# EEG_cap_final.net
KiCad netlist of a schematic drawn in EAGLE
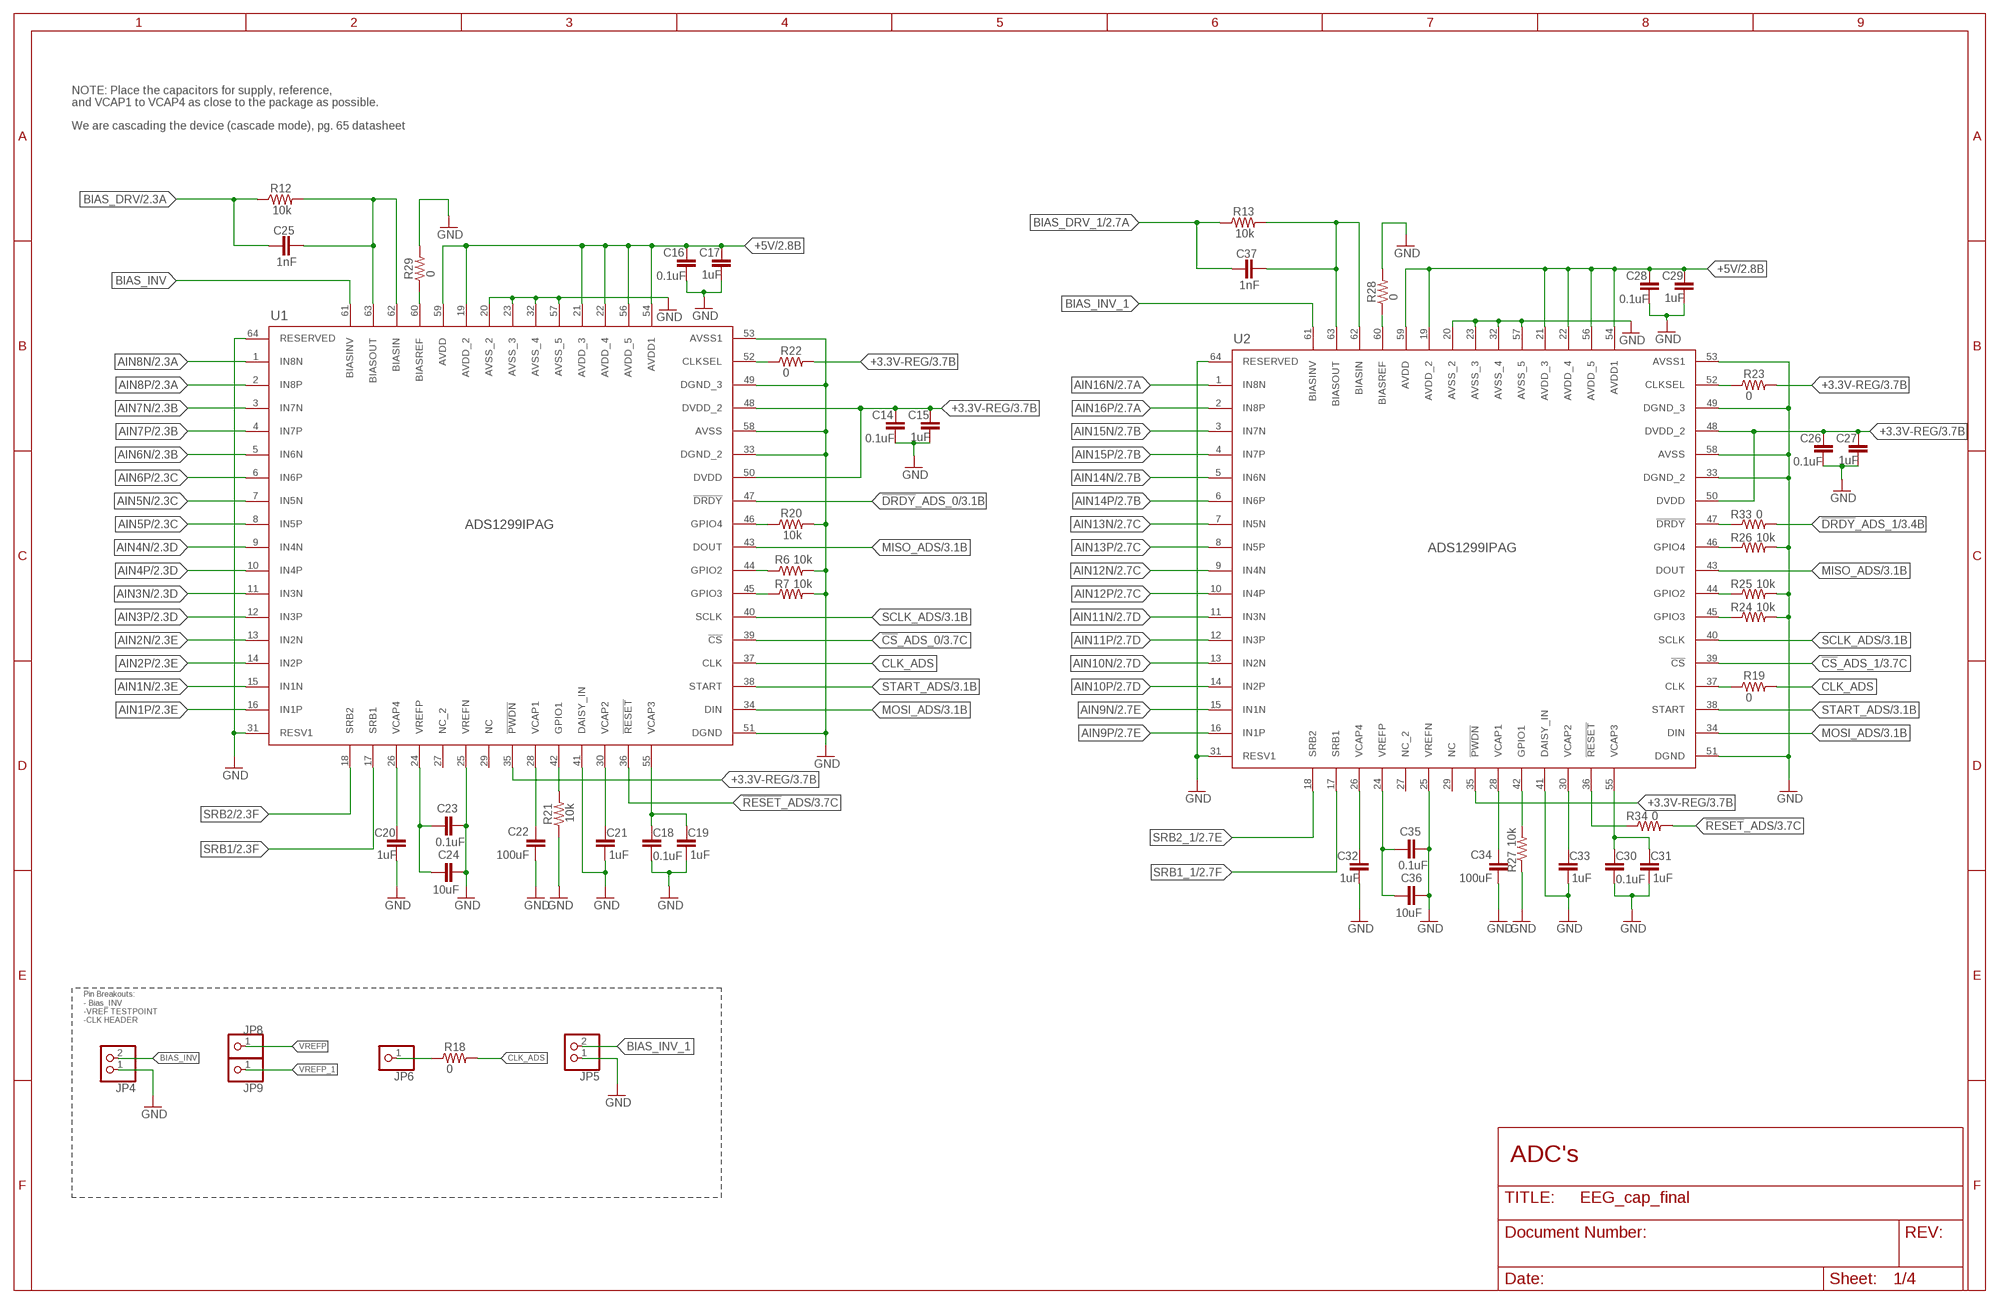
[diagram p0: schematic, sheet 1]
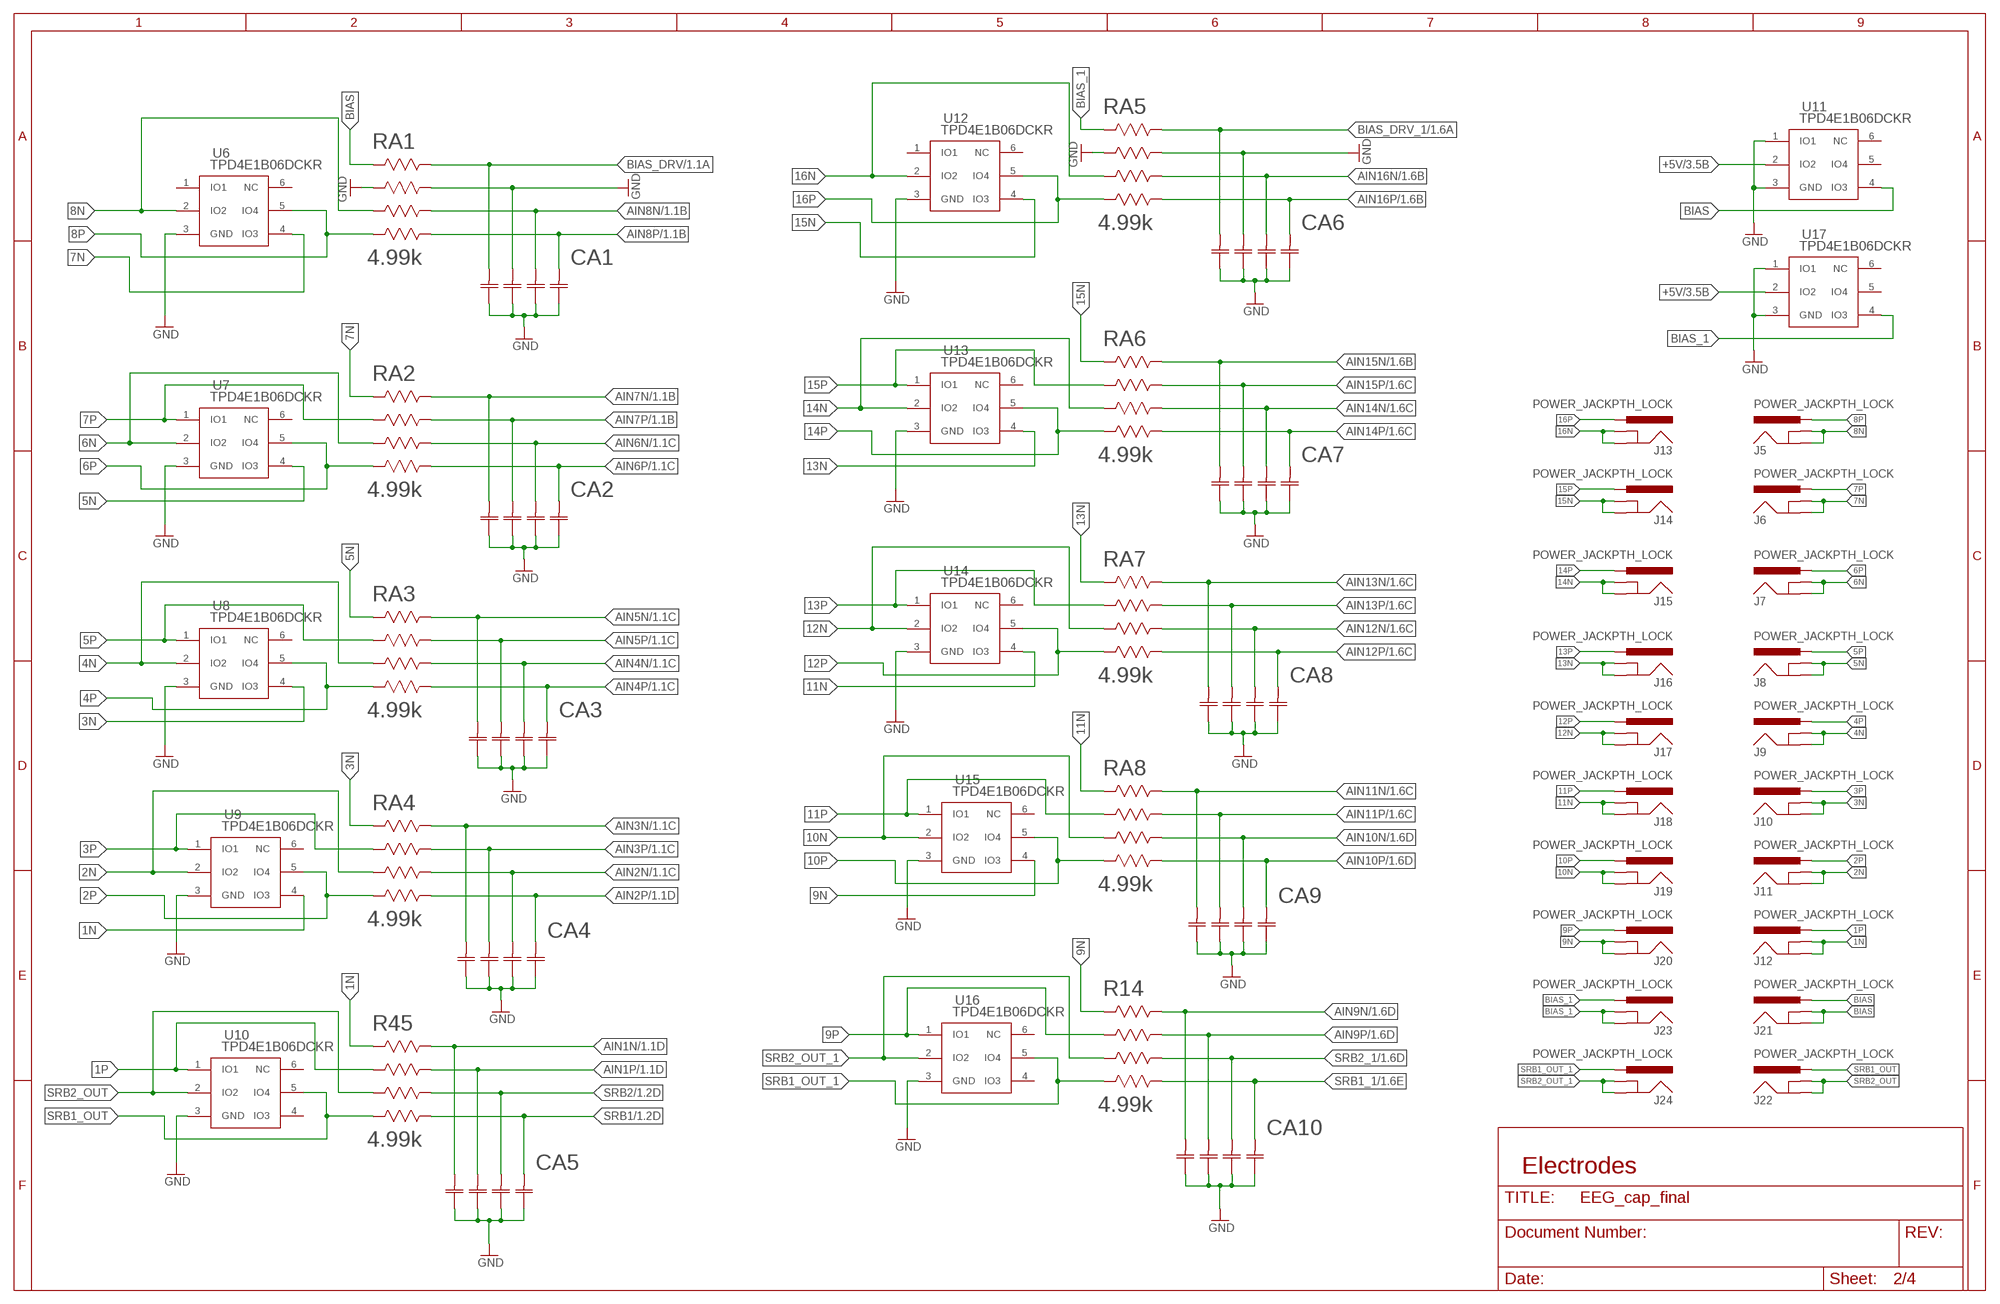
[diagram p1: schematic, sheet 2]
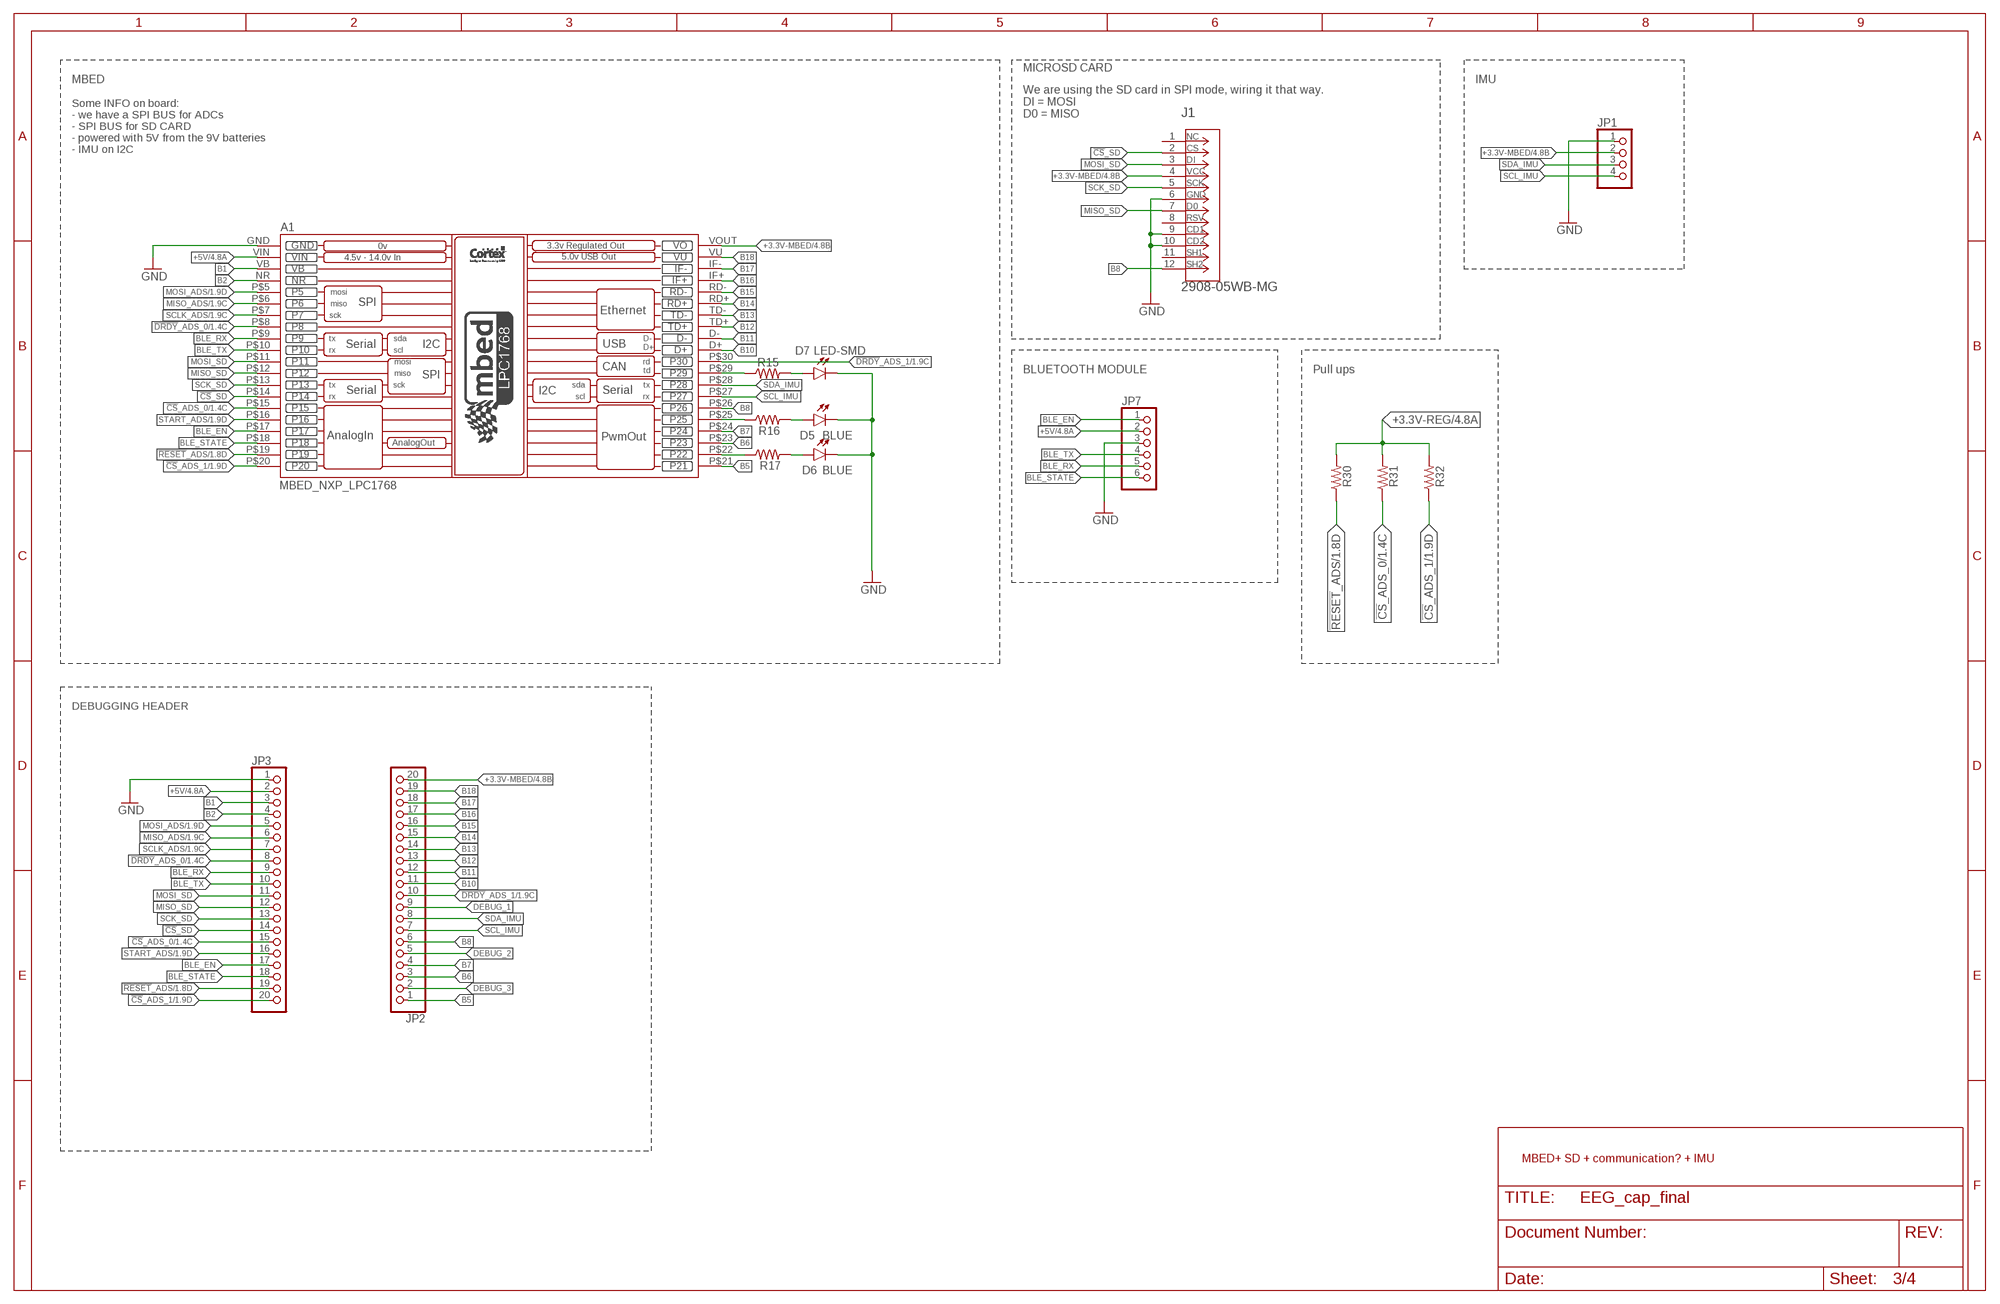
[diagram p2: schematic, sheet 3]
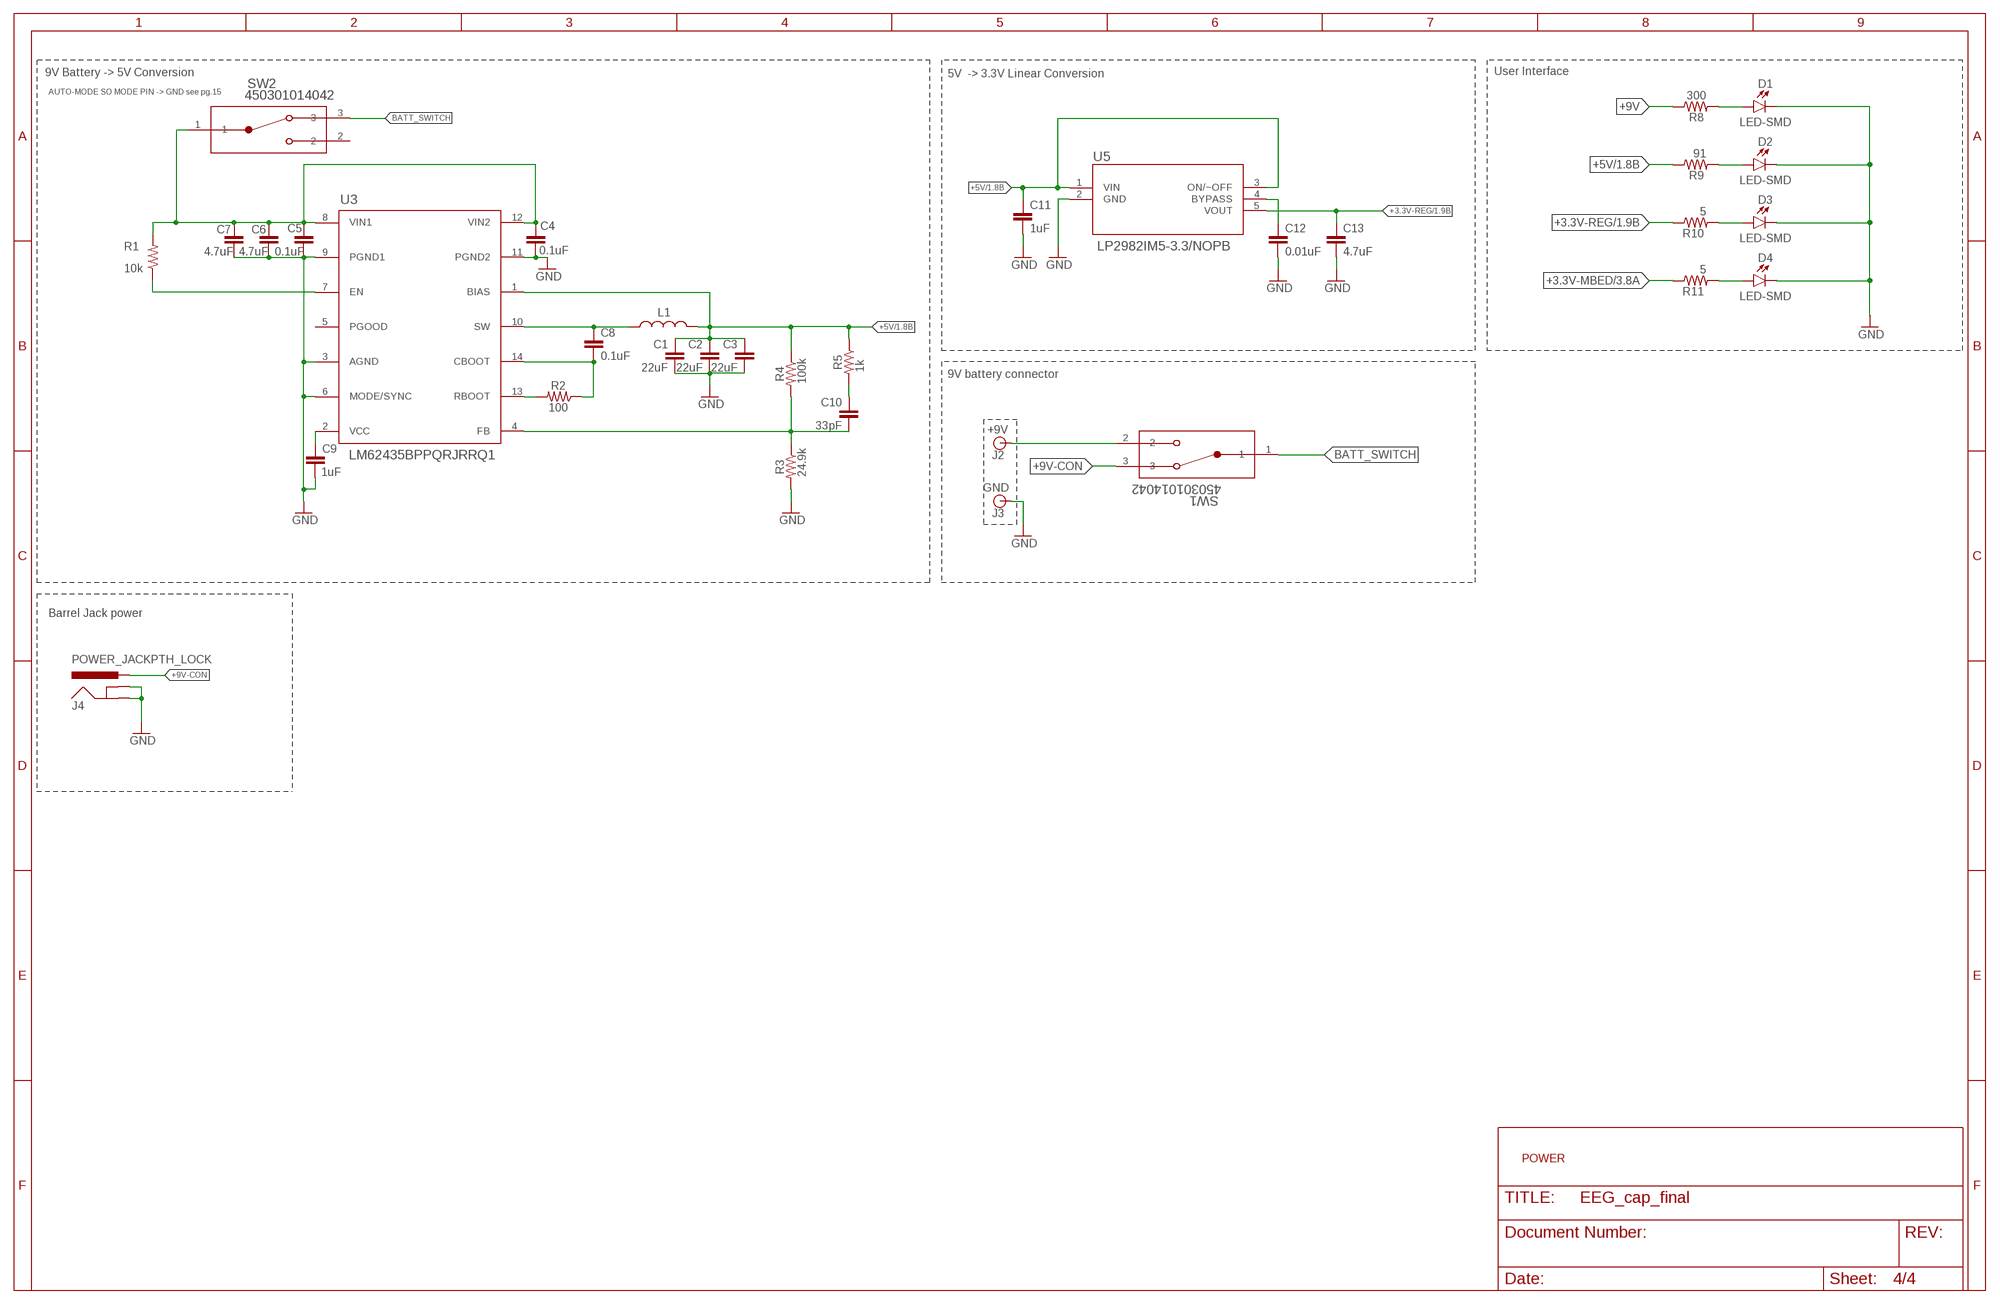
[diagram p3: schematic, sheet 4]

(export (version "E")
  (design (tool "Eeschema 10.0.6"))
  (components
    (comp (ref "C14")
      (value "0.1uF")
      (footprint "eagle-import:C0603")
      (libsource (lib "eagle-import") (part "C-EUC0603"))
    )
    (comp (ref "C15")
      (value "1uF")
      (footprint "eagle-import:C0603")
      (libsource (lib "eagle-import") (part "C-EUC0603"))
    )
    (comp (ref "C16")
      (value "0.1uF")
      (footprint "eagle-import:C0603")
      (libsource (lib "eagle-import") (part "C-EUC0603"))
    )
    (comp (ref "C17")
      (value "1uF")
      (footprint "eagle-import:C0603")
      (libsource (lib "eagle-import") (part "C-EUC0603"))
    )
    (comp (ref "C18")
      (value "0.1uF")
      (footprint "eagle-import:C0603")
      (libsource (lib "eagle-import") (part "C-EUC0603"))
    )
    (comp (ref "C19")
      (value "1uF")
      (footprint "eagle-import:C0603")
      (libsource (lib "eagle-import") (part "C-EUC0603"))
    )
    (comp (ref "C20")
      (value "1uF")
      (footprint "eagle-import:C0603")
      (libsource (lib "eagle-import") (part "C-EUC0603"))
    )
    (comp (ref "C21")
      (value "1uF")
      (footprint "eagle-import:C0603")
      (libsource (lib "eagle-import") (part "C-EUC0603"))
    )
    (comp (ref "C22")
      (value "100uF")
      (footprint "eagle-import:C1210")
      (libsource (lib "eagle-import") (part "C-EUC1210"))
    )
    (comp (ref "C23")
      (value "0.1uF")
      (footprint "eagle-import:C0603")
      (libsource (lib "eagle-import") (part "C-EUC0603"))
    )
    (comp (ref "C24")
      (value "10uF")
      (footprint "eagle-import:C0805")
      (libsource (lib "eagle-import") (part "C-EUC0805"))
    )
    (comp (ref "C25")
      (value "1nF")
      (footprint "eagle-import:C0603")
      (libsource (lib "eagle-import") (part "C-EUC0603"))
    )
    (comp (ref "C26")
      (value "0.1uF")
      (footprint "eagle-import:C0603")
      (libsource (lib "eagle-import") (part "C-EUC0603"))
    )
    (comp (ref "C27")
      (value "1uF")
      (footprint "eagle-import:C0603")
      (libsource (lib "eagle-import") (part "C-EUC0603"))
    )
    (comp (ref "C28")
      (value "0.1uF")
      (footprint "eagle-import:C0603")
      (libsource (lib "eagle-import") (part "C-EUC0603"))
    )
    (comp (ref "C29")
      (value "1uF")
      (footprint "eagle-import:C0603")
      (libsource (lib "eagle-import") (part "C-EUC0603"))
    )
    (comp (ref "C30")
      (value "0.1uF")
      (footprint "eagle-import:C0603")
      (libsource (lib "eagle-import") (part "C-EUC0603"))
    )
    (comp (ref "C31")
      (value "1uF")
      (footprint "eagle-import:C0603")
      (libsource (lib "eagle-import") (part "C-EUC0603"))
    )
    (comp (ref "C32")
      (value "1uF")
      (footprint "eagle-import:C0603")
      (libsource (lib "eagle-import") (part "C-EUC0603"))
    )
    (comp (ref "C33")
      (value "1uF")
      (footprint "eagle-import:C0603")
      (libsource (lib "eagle-import") (part "C-EUC0603"))
    )
    (comp (ref "C34")
      (value "100uF")
      (footprint "eagle-import:C1210")
      (libsource (lib "eagle-import") (part "C-EUC1210"))
    )
    (comp (ref "C35")
      (value "0.1uF")
      (footprint "eagle-import:C0603")
      (libsource (lib "eagle-import") (part "C-EUC0603"))
    )
    (comp (ref "C36")
      (value "10uF")
      (footprint "eagle-import:C0805")
      (libsource (lib "eagle-import") (part "C-EUC0805"))
    )
    (comp (ref "C37")
      (value "1nF")
      (footprint "eagle-import:C0603")
      (libsource (lib "eagle-import") (part "C-EUC0603"))
    )
    (comp (ref "JP4")
      (value "PINHD-1X2")
      (footprint "eagle-import:1X02")
      (libsource (lib "eagle-import") (part "PINHD-1X2"))
    )
    (comp (ref "JP5")
      (value "PINHD-1X2")
      (footprint "eagle-import:1X02")
      (libsource (lib "eagle-import") (part "PINHD-1X2"))
    )
    (comp (ref "JP6")
      (value "PINHD-1X1")
      (footprint "eagle-import:1X01")
      (libsource (lib "eagle-import") (part "PINHD-1X1"))
    )
    (comp (ref "JP8")
      (value "PINHD-1X1")
      (footprint "eagle-import:1X01")
      (libsource (lib "eagle-import") (part "PINHD-1X1"))
    )
    (comp (ref "JP9")
      (value "PINHD-1X1")
      (footprint "eagle-import:1X01")
      (libsource (lib "eagle-import") (part "PINHD-1X1"))
    )
    (comp (ref "R6")
      (value "10k")
      (footprint "eagle-import:R0805")
      (libsource (lib "eagle-import") (part "R-US_R0805"))
    )
    (comp (ref "R7")
      (value "10k")
      (footprint "eagle-import:R0805")
      (libsource (lib "eagle-import") (part "R-US_R0805"))
    )
    (comp (ref "R12")
      (value "10k")
      (footprint "eagle-import:R0805")
      (libsource (lib "eagle-import") (part "R-US_R0805"))
    )
    (comp (ref "R13")
      (value "10k")
      (footprint "eagle-import:R0805")
      (libsource (lib "eagle-import") (part "R-US_R0805"))
    )
    (comp (ref "R18")
      (value "0")
      (footprint "eagle-import:R0805")
      (libsource (lib "eagle-import") (part "R-US_R0805"))
    )
    (comp (ref "R19")
      (value "0")
      (footprint "eagle-import:R0805")
      (libsource (lib "eagle-import") (part "R-US_R0805"))
    )
    (comp (ref "R20")
      (value "10k")
      (footprint "eagle-import:R0805")
      (libsource (lib "eagle-import") (part "R-US_R0805"))
    )
    (comp (ref "R21")
      (value "10k")
      (footprint "eagle-import:R0805")
      (libsource (lib "eagle-import") (part "R-US_R0805"))
    )
    (comp (ref "R22")
      (value "0")
      (footprint "eagle-import:R0805")
      (libsource (lib "eagle-import") (part "R-US_R0805"))
    )
    (comp (ref "R23")
      (value "0")
      (footprint "eagle-import:R0805")
      (libsource (lib "eagle-import") (part "R-US_R0805"))
    )
    (comp (ref "R24")
      (value "10k")
      (footprint "eagle-import:R0805")
      (libsource (lib "eagle-import") (part "R-US_R0805"))
    )
    (comp (ref "R25")
      (value "10k")
      (footprint "eagle-import:R0805")
      (libsource (lib "eagle-import") (part "R-US_R0805"))
    )
    (comp (ref "R26")
      (value "10k")
      (footprint "eagle-import:R0805")
      (libsource (lib "eagle-import") (part "R-US_R0805"))
    )
    (comp (ref "R27")
      (value "10k")
      (footprint "eagle-import:R0805")
      (libsource (lib "eagle-import") (part "R-US_R0805"))
    )
    (comp (ref "R28")
      (value "0")
      (footprint "eagle-import:R0805")
      (libsource (lib "eagle-import") (part "R-US_R0805"))
    )
    (comp (ref "R29")
      (value "0")
      (footprint "eagle-import:R0805")
      (libsource (lib "eagle-import") (part "R-US_R0805"))
    )
    (comp (ref "R33")
      (value "0")
      (footprint "eagle-import:R0805")
      (libsource (lib "eagle-import") (part "R-US_R0805"))
    )
    (comp (ref "R34")
      (value "0")
      (footprint "eagle-import:R0805")
      (libsource (lib "eagle-import") (part "R-US_R0805"))
    )
    (comp (ref "U1")
      (value "ADS1299IPAG")
      (footprint "eagle-import:PAG64_TEX")
      (fields (field (name "COPYRIGHT") "Copyright (C) 2021 Ultra Librarian. All rights reserved."))
      (libsource (lib "eagle-import") (part "ADS1299IPAG"))
    )
    (comp (ref "U2")
      (value "ADS1299IPAG")
      (footprint "eagle-import:PAG64_TEX")
      (fields (field (name "COPYRIGHT") "Copyright (C) 2021 Ultra Librarian. All rights reserved."))
      (libsource (lib "eagle-import") (part "ADS1299IPAG"))
    )
    (comp (ref "CA1")
      (value "4.7nF")
      (footprint "eagle-import:CAP_CA0612_3P2X1P6_YAG")
      (libsource (lib "eagle-import") (part "CAP_ARRAY"))
    )
    (comp (ref "CA2")
      (value "4.7nF")
      (footprint "eagle-import:CAP_CA0612_3P2X1P6_YAG")
      (libsource (lib "eagle-import") (part "CAP_ARRAY"))
    )
    (comp (ref "CA3")
      (value "4.7nF")
      (footprint "eagle-import:CAP_CA0612_3P2X1P6_YAG")
      (libsource (lib "eagle-import") (part "CAP_ARRAY"))
    )
    (comp (ref "CA4")
      (value "4.7nF")
      (footprint "eagle-import:CAP_CA0612_3P2X1P6_YAG")
      (libsource (lib "eagle-import") (part "CAP_ARRAY"))
    )
    (comp (ref "CA5")
      (value "4.7nF")
      (footprint "eagle-import:CAP_CA0612_3P2X1P6_YAG")
      (libsource (lib "eagle-import") (part "CAP_ARRAY"))
    )
    (comp (ref "CA6")
      (value "4.7nF")
      (footprint "eagle-import:CAP_CA0612_3P2X1P6_YAG")
      (libsource (lib "eagle-import") (part "CAP_ARRAY"))
    )
    (comp (ref "CA7")
      (value "4.7nF")
      (footprint "eagle-import:CAP_CA0612_3P2X1P6_YAG")
      (libsource (lib "eagle-import") (part "CAP_ARRAY"))
    )
    (comp (ref "CA8")
      (value "4.7nF")
      (footprint "eagle-import:CAP_CA0612_3P2X1P6_YAG")
      (libsource (lib "eagle-import") (part "CAP_ARRAY"))
    )
    (comp (ref "CA9")
      (value "4.7nF")
      (footprint "eagle-import:CAP_CA0612_3P2X1P6_YAG")
      (libsource (lib "eagle-import") (part "CAP_ARRAY"))
    )
    (comp (ref "CA10")
      (value "4.7nF")
      (footprint "eagle-import:CAP_CA0612_3P2X1P6_YAG")
      (libsource (lib "eagle-import") (part "CAP_ARRAY"))
    )
    (comp (ref "J5")
      (value "POWER_JACKPTH_LOCK")
      (footprint "eagle-import:POWER_JACK_PTH_LOCK")
      (libsource (lib "eagle-import") (part "POWER_JACKPTH_LOCK"))
    )
    (comp (ref "J6")
      (value "POWER_JACKPTH_LOCK")
      (footprint "eagle-import:POWER_JACK_PTH_LOCK")
      (libsource (lib "eagle-import") (part "POWER_JACKPTH_LOCK"))
    )
    (comp (ref "J7")
      (value "POWER_JACKPTH_LOCK")
      (footprint "eagle-import:POWER_JACK_PTH_LOCK")
      (libsource (lib "eagle-import") (part "POWER_JACKPTH_LOCK"))
    )
    (comp (ref "J8")
      (value "POWER_JACKPTH_LOCK")
      (footprint "eagle-import:POWER_JACK_PTH_LOCK")
      (libsource (lib "eagle-import") (part "POWER_JACKPTH_LOCK"))
    )
    (comp (ref "J9")
      (value "POWER_JACKPTH_LOCK")
      (footprint "eagle-import:POWER_JACK_PTH_LOCK")
      (libsource (lib "eagle-import") (part "POWER_JACKPTH_LOCK"))
    )
    (comp (ref "J10")
      (value "POWER_JACKPTH_LOCK")
      (footprint "eagle-import:POWER_JACK_PTH_LOCK")
      (libsource (lib "eagle-import") (part "POWER_JACKPTH_LOCK"))
    )
    (comp (ref "J11")
      (value "POWER_JACKPTH_LOCK")
      (footprint "eagle-import:POWER_JACK_PTH_LOCK")
      (libsource (lib "eagle-import") (part "POWER_JACKPTH_LOCK"))
    )
    (comp (ref "J12")
      (value "POWER_JACKPTH_LOCK")
      (footprint "eagle-import:POWER_JACK_PTH_LOCK")
      (libsource (lib "eagle-import") (part "POWER_JACKPTH_LOCK"))
    )
    (comp (ref "J13")
      (value "POWER_JACKPTH_LOCK")
      (footprint "eagle-import:POWER_JACK_PTH_LOCK")
      (libsource (lib "eagle-import") (part "POWER_JACKPTH_LOCK"))
    )
    (comp (ref "J14")
      (value "POWER_JACKPTH_LOCK")
      (footprint "eagle-import:POWER_JACK_PTH_LOCK")
      (libsource (lib "eagle-import") (part "POWER_JACKPTH_LOCK"))
    )
    (comp (ref "J15")
      (value "POWER_JACKPTH_LOCK")
      (footprint "eagle-import:POWER_JACK_PTH_LOCK")
      (libsource (lib "eagle-import") (part "POWER_JACKPTH_LOCK"))
    )
    (comp (ref "J16")
      (value "POWER_JACKPTH_LOCK")
      (footprint "eagle-import:POWER_JACK_PTH_LOCK")
      (libsource (lib "eagle-import") (part "POWER_JACKPTH_LOCK"))
    )
    (comp (ref "J17")
      (value "POWER_JACKPTH_LOCK")
      (footprint "eagle-import:POWER_JACK_PTH_LOCK")
      (libsource (lib "eagle-import") (part "POWER_JACKPTH_LOCK"))
    )
    (comp (ref "J18")
      (value "POWER_JACKPTH_LOCK")
      (footprint "eagle-import:POWER_JACK_PTH_LOCK")
      (libsource (lib "eagle-import") (part "POWER_JACKPTH_LOCK"))
    )
    (comp (ref "J19")
      (value "POWER_JACKPTH_LOCK")
      (footprint "eagle-import:POWER_JACK_PTH_LOCK")
      (libsource (lib "eagle-import") (part "POWER_JACKPTH_LOCK"))
    )
    (comp (ref "J20")
      (value "POWER_JACKPTH_LOCK")
      (footprint "eagle-import:POWER_JACK_PTH_LOCK")
      (libsource (lib "eagle-import") (part "POWER_JACKPTH_LOCK"))
    )
    (comp (ref "J21")
      (value "POWER_JACKPTH_LOCK")
      (footprint "eagle-import:POWER_JACK_PTH_LOCK")
      (libsource (lib "eagle-import") (part "POWER_JACKPTH_LOCK"))
    )
    (comp (ref "J22")
      (value "POWER_JACKPTH_LOCK")
      (footprint "eagle-import:POWER_JACK_PTH_LOCK")
      (libsource (lib "eagle-import") (part "POWER_JACKPTH_LOCK"))
    )
    (comp (ref "J23")
      (value "POWER_JACKPTH_LOCK")
      (footprint "eagle-import:POWER_JACK_PTH_LOCK")
      (libsource (lib "eagle-import") (part "POWER_JACKPTH_LOCK"))
    )
    (comp (ref "J24")
      (value "POWER_JACKPTH_LOCK")
      (footprint "eagle-import:POWER_JACK_PTH_LOCK")
      (libsource (lib "eagle-import") (part "POWER_JACKPTH_LOCK"))
    )
    (comp (ref "R14")
      (value "4.99k")
      (footprint "eagle-import:BO_CAT16")
      (fields
        (field (name "MANUFACTURER_PART_NUMBER") "CAT16-220J4LF")
        (field (name "COPYRIGHT") "Copyright (C) 2021 Ultra Librarian. All rights reserved.")
      )
      (libsource (lib "eagle-import") (part "CAT16-220J4LF"))
    )
    (comp (ref "R45")
      (value "4.99k")
      (footprint "eagle-import:BO_CAT16")
      (fields
        (field (name "MANUFACTURER_PART_NUMBER") "CAT16-220J4LF")
        (field (name "COPYRIGHT") "Copyright (C) 2021 Ultra Librarian. All rights reserved.")
      )
      (libsource (lib "eagle-import") (part "CAT16-220J4LF"))
    )
    (comp (ref "RA1")
      (value "4.99k")
      (footprint "eagle-import:BO_CAT16")
      (fields
        (field (name "MANUFACTURER_PART_NUMBER") "CAT16-220J4LF")
        (field (name "COPYRIGHT") "Copyright (C) 2021 Ultra Librarian. All rights reserved.")
      )
      (libsource (lib "eagle-import") (part "CAT16-220J4LF"))
    )
    (comp (ref "RA2")
      (value "4.99k")
      (footprint "eagle-import:BO_CAT16")
      (fields
        (field (name "MANUFACTURER_PART_NUMBER") "CAT16-220J4LF")
        (field (name "COPYRIGHT") "Copyright (C) 2021 Ultra Librarian. All rights reserved.")
      )
      (libsource (lib "eagle-import") (part "CAT16-220J4LF"))
    )
    (comp (ref "RA3")
      (value "4.99k")
      (footprint "eagle-import:BO_CAT16")
      (fields
        (field (name "MANUFACTURER_PART_NUMBER") "CAT16-220J4LF")
        (field (name "COPYRIGHT") "Copyright (C) 2021 Ultra Librarian. All rights reserved.")
      )
      (libsource (lib "eagle-import") (part "CAT16-220J4LF"))
    )
    (comp (ref "RA4")
      (value "4.99k")
      (footprint "eagle-import:BO_CAT16")
      (fields
        (field (name "MANUFACTURER_PART_NUMBER") "CAT16-220J4LF")
        (field (name "COPYRIGHT") "Copyright (C) 2021 Ultra Librarian. All rights reserved.")
      )
      (libsource (lib "eagle-import") (part "CAT16-220J4LF"))
    )
    (comp (ref "RA5")
      (value "4.99k")
      (footprint "eagle-import:BO_CAT16")
      (fields
        (field (name "MANUFACTURER_PART_NUMBER") "CAT16-220J4LF")
        (field (name "COPYRIGHT") "Copyright (C) 2021 Ultra Librarian. All rights reserved.")
      )
      (libsource (lib "eagle-import") (part "CAT16-220J4LF"))
    )
    (comp (ref "RA6")
      (value "4.99k")
      (footprint "eagle-import:BO_CAT16")
      (fields
        (field (name "MANUFACTURER_PART_NUMBER") "CAT16-220J4LF")
        (field (name "COPYRIGHT") "Copyright (C) 2021 Ultra Librarian. All rights reserved.")
      )
      (libsource (lib "eagle-import") (part "CAT16-220J4LF"))
    )
    (comp (ref "RA7")
      (value "4.99k")
      (footprint "eagle-import:BO_CAT16")
      (fields
        (field (name "MANUFACTURER_PART_NUMBER") "CAT16-220J4LF")
        (field (name "COPYRIGHT") "Copyright (C) 2021 Ultra Librarian. All rights reserved.")
      )
      (libsource (lib "eagle-import") (part "CAT16-220J4LF"))
    )
    (comp (ref "RA8")
      (value "4.99k")
      (footprint "eagle-import:BO_CAT16")
      (fields
        (field (name "MANUFACTURER_PART_NUMBER") "CAT16-220J4LF")
        (field (name "COPYRIGHT") "Copyright (C) 2021 Ultra Librarian. All rights reserved.")
      )
      (libsource (lib "eagle-import") (part "CAT16-220J4LF"))
    )
    (comp (ref "U6")
      (value "TPD4E1B06DCKR")
      (footprint "eagle-import:DCK6_TEX")
      (fields (field (name "COPYRIGHT") "Copyright (C) 2021 Ultra Librarian. All rights reserved."))
      (libsource (lib "eagle-import") (part "TPD4E1B06DCKR"))
    )
    (comp (ref "U7")
      (value "TPD4E1B06DCKR")
      (footprint "eagle-import:DCK6_TEX")
      (fields (field (name "COPYRIGHT") "Copyright (C) 2021 Ultra Librarian. All rights reserved."))
      (libsource (lib "eagle-import") (part "TPD4E1B06DCKR"))
    )
    (comp (ref "U8")
      (value "TPD4E1B06DCKR")
      (footprint "eagle-import:DCK6_TEX")
      (fields (field (name "COPYRIGHT") "Copyright (C) 2021 Ultra Librarian. All rights reserved."))
      (libsource (lib "eagle-import") (part "TPD4E1B06DCKR"))
    )
    (comp (ref "U9")
      (value "TPD4E1B06DCKR")
      (footprint "eagle-import:DCK6_TEX")
      (fields (field (name "COPYRIGHT") "Copyright (C) 2021 Ultra Librarian. All rights reserved."))
      (libsource (lib "eagle-import") (part "TPD4E1B06DCKR"))
    )
    (comp (ref "U10")
      (value "TPD4E1B06DCKR")
      (footprint "eagle-import:DCK6_TEX")
      (fields (field (name "COPYRIGHT") "Copyright (C) 2021 Ultra Librarian. All rights reserved."))
      (libsource (lib "eagle-import") (part "TPD4E1B06DCKR"))
    )
    (comp (ref "U11")
      (value "TPD4E1B06DCKR")
      (footprint "eagle-import:DCK6_TEX")
      (fields (field (name "COPYRIGHT") "Copyright (C) 2021 Ultra Librarian. All rights reserved."))
      (libsource (lib "eagle-import") (part "TPD4E1B06DCKR"))
    )
    (comp (ref "U12")
      (value "TPD4E1B06DCKR")
      (footprint "eagle-import:DCK6_TEX")
      (fields (field (name "COPYRIGHT") "Copyright (C) 2021 Ultra Librarian. All rights reserved."))
      (libsource (lib "eagle-import") (part "TPD4E1B06DCKR"))
    )
    (comp (ref "U13")
      (value "TPD4E1B06DCKR")
      (footprint "eagle-import:DCK6_TEX")
      (fields (field (name "COPYRIGHT") "Copyright (C) 2021 Ultra Librarian. All rights reserved."))
      (libsource (lib "eagle-import") (part "TPD4E1B06DCKR"))
    )
    (comp (ref "U14")
      (value "TPD4E1B06DCKR")
      (footprint "eagle-import:DCK6_TEX")
      (fields (field (name "COPYRIGHT") "Copyright (C) 2021 Ultra Librarian. All rights reserved."))
      (libsource (lib "eagle-import") (part "TPD4E1B06DCKR"))
    )
    (comp (ref "U15")
      (value "TPD4E1B06DCKR")
      (footprint "eagle-import:DCK6_TEX")
      (fields (field (name "COPYRIGHT") "Copyright (C) 2021 Ultra Librarian. All rights reserved."))
      (libsource (lib "eagle-import") (part "TPD4E1B06DCKR"))
    )
    (comp (ref "U16")
      (value "TPD4E1B06DCKR")
      (footprint "eagle-import:DCK6_TEX")
      (fields (field (name "COPYRIGHT") "Copyright (C) 2021 Ultra Librarian. All rights reserved."))
      (libsource (lib "eagle-import") (part "TPD4E1B06DCKR"))
    )
    (comp (ref "U17")
      (value "TPD4E1B06DCKR")
      (footprint "eagle-import:DCK6_TEX")
      (fields (field (name "COPYRIGHT") "Copyright (C) 2021 Ultra Librarian. All rights reserved."))
      (libsource (lib "eagle-import") (part "TPD4E1B06DCKR"))
    )
    (comp (ref "A1")
      (value "MBED_NXP_LPC1768")
      (footprint "eagle-import:MBED_LPC1768")
      (libsource (lib "eagle-import") (part "MBED_NXP_LPC1768"))
    )
    (comp (ref "D5")
      (value "BLUE")
      (footprint "eagle-import:LED0603")
      (libsource (lib "eagle-import") (part "LED-SMD"))
    )
    (comp (ref "D6")
      (value "BLUE")
      (footprint "eagle-import:LED0603")
      (libsource (lib "eagle-import") (part "LED-SMD"))
    )
    (comp (ref "D7")
      (value "LED-SMD")
      (footprint "eagle-import:LED0603")
      (libsource (lib "eagle-import") (part "LED-SMD"))
    )
    (comp (ref "J1")
      (value "2908-05WB-MG")
      (footprint "eagle-import:CONN_3M_2900")
      (fields (field (name "COPYRIGHT") "Copyright (C) 2021 Ultra Librarian. All rights reserved."))
      (libsource (lib "eagle-import") (part "2908-05WB-MG"))
    )
    (comp (ref "JP1")
      (value "PINHD-1X4")
      (footprint "eagle-import:1X04")
      (libsource (lib "eagle-import") (part "PINHD-1X4"))
    )
    (comp (ref "JP2")
      (value "PINHD-1X20")
      (footprint "eagle-import:1X20")
      (libsource (lib "eagle-import") (part "PINHD-1X20"))
    )
    (comp (ref "JP3")
      (value "PINHD-1X20")
      (footprint "eagle-import:1X20")
      (libsource (lib "eagle-import") (part "PINHD-1X20"))
    )
    (comp (ref "JP7")
      (value "PINHD-1X6")
      (footprint "eagle-import:1X06")
      (libsource (lib "eagle-import") (part "PINHD-1X6"))
    )
    (comp (ref "R15")
      (value "1k")
      (footprint "eagle-import:R0805")
      (libsource (lib "eagle-import") (part "R-US_R0805"))
    )
    (comp (ref "R16")
      (value "1k")
      (footprint "eagle-import:R0805")
      (libsource (lib "eagle-import") (part "R-US_R0805"))
    )
    (comp (ref "R17")
      (value "1k")
      (footprint "eagle-import:R0805")
      (libsource (lib "eagle-import") (part "R-US_R0805"))
    )
    (comp (ref "R30")
      (value "10k")
      (footprint "eagle-import:R0805")
      (libsource (lib "eagle-import") (part "R-US_R0805"))
    )
    (comp (ref "R31")
      (value "1k")
      (footprint "eagle-import:R0805")
      (libsource (lib "eagle-import") (part "R-US_R0805"))
    )
    (comp (ref "R32")
      (value "1k")
      (footprint "eagle-import:R0805")
      (libsource (lib "eagle-import") (part "R-US_R0805"))
    )
    (comp (ref "C1")
      (value "22uF")
      (footprint "eagle-import:C0805")
      (libsource (lib "eagle-import") (part "C-EUC0805"))
    )
    (comp (ref "C2")
      (value "22uF")
      (footprint "eagle-import:C0805")
      (libsource (lib "eagle-import") (part "C-EUC0805"))
    )
    (comp (ref "C3")
      (value "22uF")
      (footprint "eagle-import:C0805")
      (libsource (lib "eagle-import") (part "C-EUC0805"))
    )
    (comp (ref "C4")
      (value "0.1uF")
      (footprint "eagle-import:C0805")
      (libsource (lib "eagle-import") (part "C-EUC0805"))
    )
    (comp (ref "C5")
      (value "0.1uF")
      (footprint "eagle-import:C0805")
      (libsource (lib "eagle-import") (part "C-EUC0805"))
    )
    (comp (ref "C6")
      (value "4.7uF")
      (footprint "eagle-import:C0805")
      (libsource (lib "eagle-import") (part "C-EUC0805"))
    )
    (comp (ref "C7")
      (value "4.7uF")
      (footprint "eagle-import:C0805")
      (libsource (lib "eagle-import") (part "C-EUC0805"))
    )
    (comp (ref "C8")
      (value "0.1uF")
      (footprint "eagle-import:C0805")
      (libsource (lib "eagle-import") (part "C-EUC0805"))
    )
    (comp (ref "C9")
      (value "1uF")
      (footprint "eagle-import:C0805")
      (libsource (lib "eagle-import") (part "C-EUC0805"))
    )
    (comp (ref "C10")
      (value "33pF")
      (footprint "eagle-import:C0805")
      (libsource (lib "eagle-import") (part "C-EUC0805"))
    )
    (comp (ref "C11")
      (value "1uF")
      (footprint "eagle-import:C0805")
      (libsource (lib "eagle-import") (part "C-EUC0805"))
    )
    (comp (ref "C12")
      (value "0.01uF")
      (footprint "eagle-import:C0805")
      (libsource (lib "eagle-import") (part "C-EUC0805"))
    )
    (comp (ref "C13")
      (value "4.7uF")
      (footprint "eagle-import:C0805")
      (libsource (lib "eagle-import") (part "C-EUC0805"))
    )
    (comp (ref "D1")
      (value "LED-SMD")
      (footprint "eagle-import:LED0603")
      (libsource (lib "eagle-import") (part "LED-SMD"))
    )
    (comp (ref "D2")
      (value "LED-SMD")
      (footprint "eagle-import:LED0603")
      (libsource (lib "eagle-import") (part "LED-SMD"))
    )
    (comp (ref "D3")
      (value "LED-SMD")
      (footprint "eagle-import:LED0603")
      (libsource (lib "eagle-import") (part "LED-SMD"))
    )
    (comp (ref "D4")
      (value "LED-SMD")
      (footprint "eagle-import:LED0603")
      (libsource (lib "eagle-import") (part "LED-SMD"))
    )
    (comp (ref "J2")
      (value "+9V")
      (footprint "eagle-import:BANANA_CONN")
      (libsource (lib "eagle-import") (part "BANANA_CONN"))
    )
    (comp (ref "J3")
      (value "GND")
      (footprint "eagle-import:BANANA_CONN")
      (libsource (lib "eagle-import") (part "BANANA_CONN"))
    )
    (comp (ref "J4")
      (value "POWER_JACKPTH_LOCK")
      (footprint "eagle-import:POWER_JACK_PTH_LOCK")
      (libsource (lib "eagle-import") (part "POWER_JACKPTH_LOCK"))
    )
    (comp (ref "L1")
      (value "DFE252010P-1R5M=P2")
      (footprint "eagle-import:INDC2520X100N")
      (fields (field (name "DIGI-KEY_PART_NUMBER") "490-10636-1-ND") (field (name "MF") "Murata"))
      (libsource (lib "eagle-import") (part "DFE252010P-1R5M=P2"))
    )
    (comp (ref "R1")
      (value "10k")
      (footprint "eagle-import:R0805")
      (libsource (lib "eagle-import") (part "R-US_R0805"))
    )
    (comp (ref "R2")
      (value "100")
      (footprint "eagle-import:R0805")
      (libsource (lib "eagle-import") (part "R-US_R0805"))
    )
    (comp (ref "R3")
      (value "24.9k")
      (footprint "eagle-import:R0805")
      (libsource (lib "eagle-import") (part "R-US_R0805"))
    )
    (comp (ref "R4")
      (value "100k")
      (footprint "eagle-import:R0805")
      (libsource (lib "eagle-import") (part "R-US_R0805"))
    )
    (comp (ref "R5")
      (value "1k")
      (footprint "eagle-import:R0805")
      (libsource (lib "eagle-import") (part "R-US_R0805"))
    )
    (comp (ref "R8")
      (value "300")
      (footprint "eagle-import:R0805")
      (libsource (lib "eagle-import") (part "R-US_R0805"))
    )
    (comp (ref "R9")
      (value "91")
      (footprint "eagle-import:R0805")
      (libsource (lib "eagle-import") (part "R-US_R0805"))
    )
    (comp (ref "R10")
      (value "5")
      (footprint "eagle-import:R0805")
      (libsource (lib "eagle-import") (part "R-US_R0805"))
    )
    (comp (ref "R11")
      (value "5")
      (footprint "eagle-import:R0805")
      (libsource (lib "eagle-import") (part "R-US_R0805"))
    )
    (comp (ref "SW1")
      (value "450301014042")
      (footprint "eagle-import:SW_450301014042_WRE")
      (fields (field (name "COPYRIGHT") "Copyright (C) 2021 Ultra Librarian. All rights reserved."))
      (libsource (lib "eagle-import") (part "450301014042"))
    )
    (comp (ref "SW2")
      (value "450301014042")
      (footprint "eagle-import:SW_450301014042_WRE")
      (fields (field (name "COPYRIGHT") "Copyright (C) 2021 Ultra Librarian. All rights reserved."))
      (libsource (lib "eagle-import") (part "450301014042"))
    )
    (comp (ref "U3")
      (value "LM62435BPPQRJRRQ1")
      (footprint "eagle-import:VQFN-HR14_RJR_TEX")
      (fields (field (name "COPYRIGHT") "Copyright (C) 2021 Ultra Librarian. All rights reserved."))
      (libsource (lib "eagle-import") (part "LM62435BPPQRJRRQ1"))
    )
    (comp (ref "U5")
      (value "LP2982IM5-3.3/NOPB")
      (footprint "eagle-import:MF05A")
      (fields (field (name "COPYRIGHT") "Copyright (C) 2021 Ultra Librarian. All rights reserved."))
      (libsource (lib "eagle-import") (part "LP2982IM5-3.3/NOPB"))
    )
  )
  (nets
    (net (code "1") (name "+3.3V-MBED") (class "Default")
      (node (ref "A1") (pin "VOUT") (pinfunction "VO_VOUT") (pintype "passive"))
      (node (ref "J1") (pin "4") (pinfunction "4_4") (pintype "passive"))
      (node (ref "JP1") (pin "2") (pinfunction "2_2") (pintype "passive"))
      (node (ref "JP2") (pin "20") (pinfunction "20_20") (pintype "passive"))
      (node (ref "R11") (pin "1") (pinfunction "1_1") (pintype "passive"))
    )
    (net (code "2") (name "+3.3V-REG") (class "Default")
      (node (ref "C13") (pin "1") (pinfunction "1_1") (pintype "passive"))
      (node (ref "C14") (pin "1") (pinfunction "1_1") (pintype "passive"))
      (node (ref "C15") (pin "1") (pinfunction "1_1") (pintype "passive"))
      (node (ref "C26") (pin "1") (pinfunction "1_1") (pintype "passive"))
      (node (ref "C27") (pin "1") (pinfunction "1_1") (pintype "passive"))
      (node (ref "R10") (pin "1") (pinfunction "1_1") (pintype "passive"))
      (node (ref "R22") (pin "2") (pinfunction "2_2") (pintype "passive"))
      (node (ref "R23") (pin "2") (pinfunction "2_2") (pintype "passive"))
      (node (ref "R30") (pin "2") (pinfunction "2_2") (pintype "passive"))
      (node (ref "R31") (pin "2") (pinfunction "2_2") (pintype "passive"))
      (node (ref "R32") (pin "2") (pinfunction "2_2") (pintype "passive"))
      (node (ref "U1") (pin "35") (pinfunction "~{PWDN}_35") (pintype "power_in"))
      (node (ref "U1") (pin "48") (pinfunction "DVDD_2_48") (pintype "power_in"))
      (node (ref "U1") (pin "50") (pinfunction "DVDD_50") (pintype "power_in"))
      (node (ref "U2") (pin "35") (pinfunction "~{PWDN}_35") (pintype "power_in"))
      (node (ref "U2") (pin "48") (pinfunction "DVDD_2_48") (pintype "power_in"))
      (node (ref "U2") (pin "50") (pinfunction "DVDD_50") (pintype "power_in"))
      (node (ref "U5") (pin "5") (pinfunction "VOUT_5") (pintype "output"))
    )
    (net (code "3") (name "+5V") (class "Default")
      (node (ref "A1") (pin "VIN") (pinfunction "VIN_VIN") (pintype "passive"))
      (node (ref "C1") (pin "1") (pinfunction "1_1") (pintype "passive"))
      (node (ref "C11") (pin "1") (pinfunction "1_1") (pintype "passive"))
      (node (ref "C16") (pin "1") (pinfunction "1_1") (pintype "passive"))
      (node (ref "C17") (pin "1") (pinfunction "1_1") (pintype "passive"))
      (node (ref "C2") (pin "1") (pinfunction "1_1") (pintype "passive"))
      (node (ref "C28") (pin "1") (pinfunction "1_1") (pintype "passive"))
      (node (ref "C29") (pin "1") (pinfunction "1_1") (pintype "passive"))
      (node (ref "C3") (pin "1") (pinfunction "1_1") (pintype "passive"))
      (node (ref "JP3") (pin "2") (pinfunction "2_2") (pintype "passive"))
      (node (ref "JP7") (pin "2") (pinfunction "2_2") (pintype "passive"))
      (node (ref "L1") (pin "2") (pinfunction "2_2") (pintype "passive"))
      (node (ref "R4") (pin "1") (pinfunction "1_1") (pintype "passive"))
      (node (ref "R5") (pin "1") (pinfunction "1_1") (pintype "passive"))
      (node (ref "R9") (pin "1") (pinfunction "1_1") (pintype "passive"))
      (node (ref "U1") (pin "19") (pinfunction "AVDD_2_19") (pintype "power_in"))
      (node (ref "U1") (pin "21") (pinfunction "AVDD_3_21") (pintype "power_in"))
      (node (ref "U1") (pin "22") (pinfunction "AVDD_4_22") (pintype "power_in"))
      (node (ref "U1") (pin "54") (pinfunction "AVDD1_54") (pintype "power_in"))
      (node (ref "U1") (pin "56") (pinfunction "AVDD_5_56") (pintype "power_in"))
      (node (ref "U1") (pin "59") (pinfunction "AVDD_59") (pintype "power_in"))
      (node (ref "U11") (pin "2") (pinfunction "IO2_2") (pintype "bidirectional"))
      (node (ref "U17") (pin "2") (pinfunction "IO2_2") (pintype "bidirectional"))
      (node (ref "U2") (pin "19") (pinfunction "AVDD_2_19") (pintype "power_in"))
      (node (ref "U2") (pin "21") (pinfunction "AVDD_3_21") (pintype "power_in"))
      (node (ref "U2") (pin "22") (pinfunction "AVDD_4_22") (pintype "power_in"))
      (node (ref "U2") (pin "54") (pinfunction "AVDD1_54") (pintype "power_in"))
      (node (ref "U2") (pin "56") (pinfunction "AVDD_5_56") (pintype "power_in"))
      (node (ref "U2") (pin "59") (pinfunction "AVDD_59") (pintype "power_in"))
      (node (ref "U3") (pin "1") (pinfunction "BIAS_1") (pintype "passive"))
      (node (ref "U5") (pin "1") (pinfunction "VIN_1") (pintype "input"))
      (node (ref "U5") (pin "3") (pinfunction "ON/~{OFF}_3") (pintype "passive"))
    )
    (net (code "4") (name "+9V") (class "Default")
      (node (ref "C4") (pin "1") (pinfunction "1_1") (pintype "passive"))
      (node (ref "C5") (pin "1") (pinfunction "1_1") (pintype "passive"))
      (node (ref "C6") (pin "1") (pinfunction "1_1") (pintype "passive"))
      (node (ref "C7") (pin "1") (pinfunction "1_1") (pintype "passive"))
      (node (ref "R1") (pin "2") (pinfunction "2_2") (pintype "passive"))
      (node (ref "R8") (pin "1") (pinfunction "1_1") (pintype "passive"))
      (node (ref "SW2") (pin "1") (pinfunction "1_1") (pintype "passive"))
      (node (ref "U3") (pin "12") (pinfunction "VIN2_12") (pintype "input"))
      (node (ref "U3") (pin "8") (pinfunction "VIN1_8") (pintype "input"))
    )
    (net (code "5") (name "+9V-CON") (class "Default")
      (node (ref "J4") (pin "PWR") (pinfunction "PWR_PWR") (pintype "bidirectional"))
      (node (ref "SW1") (pin "3") (pinfunction "3_3") (pintype "passive"))
    )
    (net (code "6") (name "1N") (class "Default")
      (node (ref "J12") (pin "GND") (pinfunction "GND_GND") (pintype "bidirectional"))
      (node (ref "J12") (pin "GNDBREAK") (pinfunction "GNDBREAK_GNDBREAK") (pintype "bidirectional"))
      (node (ref "R45") (pin "1") (pinfunction "1_1") (pintype "passive"))
      (node (ref "U9") (pin "4") (pinfunction "IO3_4") (pintype "bidirectional"))
    )
    (net (code "7") (name "1P") (class "Default")
      (node (ref "J12") (pin "PWR") (pinfunction "PWR_PWR") (pintype "bidirectional"))
      (node (ref "R45") (pin "2") (pinfunction "2_2") (pintype "passive"))
      (node (ref "U10") (pin "1") (pinfunction "IO1_1") (pintype "bidirectional"))
    )
    (net (code "8") (name "2N") (class "Default")
      (node (ref "J11") (pin "GND") (pinfunction "GND_GND") (pintype "bidirectional"))
      (node (ref "J11") (pin "GNDBREAK") (pinfunction "GNDBREAK_GNDBREAK") (pintype "bidirectional"))
      (node (ref "RA4") (pin "3") (pinfunction "3_3") (pintype "passive"))
      (node (ref "U9") (pin "2") (pinfunction "IO2_2") (pintype "bidirectional"))
    )
    (net (code "9") (name "2P") (class "Default")
      (node (ref "J11") (pin "PWR") (pinfunction "PWR_PWR") (pintype "bidirectional"))
      (node (ref "RA4") (pin "4") (pinfunction "4_4") (pintype "passive"))
      (node (ref "U9") (pin "5") (pinfunction "IO4_5") (pintype "bidirectional"))
    )
    (net (code "10") (name "3N") (class "Default")
      (node (ref "J10") (pin "GND") (pinfunction "GND_GND") (pintype "bidirectional"))
      (node (ref "J10") (pin "GNDBREAK") (pinfunction "GNDBREAK_GNDBREAK") (pintype "bidirectional"))
      (node (ref "RA4") (pin "1") (pinfunction "1_1") (pintype "passive"))
      (node (ref "U8") (pin "4") (pinfunction "IO3_4") (pintype "bidirectional"))
    )
    (net (code "11") (name "3P") (class "Default")
      (node (ref "J10") (pin "PWR") (pinfunction "PWR_PWR") (pintype "bidirectional"))
      (node (ref "RA4") (pin "2") (pinfunction "2_2") (pintype "passive"))
      (node (ref "U9") (pin "1") (pinfunction "IO1_1") (pintype "bidirectional"))
    )
    (net (code "12") (name "4N") (class "Default")
      (node (ref "J9") (pin "GND") (pinfunction "GND_GND") (pintype "bidirectional"))
      (node (ref "J9") (pin "GNDBREAK") (pinfunction "GNDBREAK_GNDBREAK") (pintype "bidirectional"))
      (node (ref "RA3") (pin "3") (pinfunction "3_3") (pintype "passive"))
      (node (ref "U8") (pin "2") (pinfunction "IO2_2") (pintype "bidirectional"))
    )
    (net (code "13") (name "4P") (class "Default")
      (node (ref "J9") (pin "PWR") (pinfunction "PWR_PWR") (pintype "bidirectional"))
      (node (ref "RA3") (pin "4") (pinfunction "4_4") (pintype "passive"))
      (node (ref "U8") (pin "5") (pinfunction "IO4_5") (pintype "bidirectional"))
    )
    (net (code "14") (name "5N") (class "Default")
      (node (ref "J8") (pin "GND") (pinfunction "GND_GND") (pintype "bidirectional"))
      (node (ref "J8") (pin "GNDBREAK") (pinfunction "GNDBREAK_GNDBREAK") (pintype "bidirectional"))
      (node (ref "RA3") (pin "1") (pinfunction "1_1") (pintype "passive"))
      (node (ref "U7") (pin "4") (pinfunction "IO3_4") (pintype "bidirectional"))
    )
    (net (code "15") (name "5P") (class "Default")
      (node (ref "J8") (pin "PWR") (pinfunction "PWR_PWR") (pintype "bidirectional"))
      (node (ref "RA3") (pin "2") (pinfunction "2_2") (pintype "passive"))
      (node (ref "U8") (pin "1") (pinfunction "IO1_1") (pintype "bidirectional"))
    )
    (net (code "16") (name "6N") (class "Default")
      (node (ref "J7") (pin "GND") (pinfunction "GND_GND") (pintype "bidirectional"))
      (node (ref "J7") (pin "GNDBREAK") (pinfunction "GNDBREAK_GNDBREAK") (pintype "bidirectional"))
      (node (ref "RA2") (pin "3") (pinfunction "3_3") (pintype "passive"))
      (node (ref "U7") (pin "2") (pinfunction "IO2_2") (pintype "bidirectional"))
    )
    (net (code "17") (name "6P") (class "Default")
      (node (ref "J7") (pin "PWR") (pinfunction "PWR_PWR") (pintype "bidirectional"))
      (node (ref "RA2") (pin "4") (pinfunction "4_4") (pintype "passive"))
      (node (ref "U7") (pin "5") (pinfunction "IO4_5") (pintype "bidirectional"))
    )
    (net (code "18") (name "7N") (class "Default")
      (node (ref "J6") (pin "GND") (pinfunction "GND_GND") (pintype "bidirectional"))
      (node (ref "J6") (pin "GNDBREAK") (pinfunction "GNDBREAK_GNDBREAK") (pintype "bidirectional"))
      (node (ref "RA2") (pin "1") (pinfunction "1_1") (pintype "passive"))
      (node (ref "U6") (pin "4") (pinfunction "IO3_4") (pintype "bidirectional"))
    )
    (net (code "19") (name "7P") (class "Default")
      (node (ref "J6") (pin "PWR") (pinfunction "PWR_PWR") (pintype "bidirectional"))
      (node (ref "RA2") (pin "2") (pinfunction "2_2") (pintype "passive"))
      (node (ref "U7") (pin "1") (pinfunction "IO1_1") (pintype "bidirectional"))
    )
    (net (code "20") (name "8N") (class "Default")
      (node (ref "J5") (pin "GND") (pinfunction "GND_GND") (pintype "bidirectional"))
      (node (ref "J5") (pin "GNDBREAK") (pinfunction "GNDBREAK_GNDBREAK") (pintype "bidirectional"))
      (node (ref "RA1") (pin "3") (pinfunction "3_3") (pintype "passive"))
      (node (ref "U6") (pin "2") (pinfunction "IO2_2") (pintype "bidirectional"))
    )
    (net (code "21") (name "8P") (class "Default")
      (node (ref "J5") (pin "PWR") (pinfunction "PWR_PWR") (pintype "bidirectional"))
      (node (ref "RA1") (pin "4") (pinfunction "4_4") (pintype "passive"))
      (node (ref "U6") (pin "5") (pinfunction "IO4_5") (pintype "bidirectional"))
    )
    (net (code "22") (name "9N") (class "Default")
      (node (ref "J20") (pin "GND") (pinfunction "GND_GND") (pintype "bidirectional"))
      (node (ref "J20") (pin "GNDBREAK") (pinfunction "GNDBREAK_GNDBREAK") (pintype "bidirectional"))
      (node (ref "R14") (pin "1") (pinfunction "1_1") (pintype "passive"))
      (node (ref "U15") (pin "4") (pinfunction "IO3_4") (pintype "bidirectional"))
    )
    (net (code "23") (name "9P") (class "Default")
      (node (ref "J20") (pin "PWR") (pinfunction "PWR_PWR") (pintype "bidirectional"))
      (node (ref "R14") (pin "2") (pinfunction "2_2") (pintype "passive"))
      (node (ref "U16") (pin "1") (pinfunction "IO1_1") (pintype "bidirectional"))
    )
    (net (code "24") (name "10N") (class "Default")
      (node (ref "J19") (pin "GND") (pinfunction "GND_GND") (pintype "bidirectional"))
      (node (ref "J19") (pin "GNDBREAK") (pinfunction "GNDBREAK_GNDBREAK") (pintype "bidirectional"))
      (node (ref "RA8") (pin "3") (pinfunction "3_3") (pintype "passive"))
      (node (ref "U15") (pin "2") (pinfunction "IO2_2") (pintype "bidirectional"))
    )
    (net (code "25") (name "10P") (class "Default")
      (node (ref "J19") (pin "PWR") (pinfunction "PWR_PWR") (pintype "bidirectional"))
      (node (ref "RA8") (pin "4") (pinfunction "4_4") (pintype "passive"))
      (node (ref "U15") (pin "5") (pinfunction "IO4_5") (pintype "bidirectional"))
    )
    (net (code "26") (name "11N") (class "Default")
      (node (ref "J18") (pin "GND") (pinfunction "GND_GND") (pintype "bidirectional"))
      (node (ref "J18") (pin "GNDBREAK") (pinfunction "GNDBREAK_GNDBREAK") (pintype "bidirectional"))
      (node (ref "RA8") (pin "1") (pinfunction "1_1") (pintype "passive"))
      (node (ref "U14") (pin "4") (pinfunction "IO3_4") (pintype "bidirectional"))
    )
    (net (code "27") (name "11P") (class "Default")
      (node (ref "J18") (pin "PWR") (pinfunction "PWR_PWR") (pintype "bidirectional"))
      (node (ref "RA8") (pin "2") (pinfunction "2_2") (pintype "passive"))
      (node (ref "U15") (pin "1") (pinfunction "IO1_1") (pintype "bidirectional"))
    )
    (net (code "28") (name "12N") (class "Default")
      (node (ref "J17") (pin "GND") (pinfunction "GND_GND") (pintype "bidirectional"))
      (node (ref "J17") (pin "GNDBREAK") (pinfunction "GNDBREAK_GNDBREAK") (pintype "bidirectional"))
      (node (ref "RA7") (pin "3") (pinfunction "3_3") (pintype "passive"))
      (node (ref "U14") (pin "2") (pinfunction "IO2_2") (pintype "bidirectional"))
    )
    (net (code "29") (name "12P") (class "Default")
      (node (ref "J17") (pin "PWR") (pinfunction "PWR_PWR") (pintype "bidirectional"))
      (node (ref "RA7") (pin "4") (pinfunction "4_4") (pintype "passive"))
      (node (ref "U14") (pin "5") (pinfunction "IO4_5") (pintype "bidirectional"))
    )
    (net (code "30") (name "13N") (class "Default")
      (node (ref "J16") (pin "GND") (pinfunction "GND_GND") (pintype "bidirectional"))
      (node (ref "J16") (pin "GNDBREAK") (pinfunction "GNDBREAK_GNDBREAK") (pintype "bidirectional"))
      (node (ref "RA7") (pin "1") (pinfunction "1_1") (pintype "passive"))
      (node (ref "U13") (pin "4") (pinfunction "IO3_4") (pintype "bidirectional"))
    )
    (net (code "31") (name "13P") (class "Default")
      (node (ref "J16") (pin "PWR") (pinfunction "PWR_PWR") (pintype "bidirectional"))
      (node (ref "RA7") (pin "2") (pinfunction "2_2") (pintype "passive"))
      (node (ref "U14") (pin "1") (pinfunction "IO1_1") (pintype "bidirectional"))
    )
    (net (code "32") (name "14N") (class "Default")
      (node (ref "J15") (pin "GND") (pinfunction "GND_GND") (pintype "bidirectional"))
      (node (ref "J15") (pin "GNDBREAK") (pinfunction "GNDBREAK_GNDBREAK") (pintype "bidirectional"))
      (node (ref "RA6") (pin "3") (pinfunction "3_3") (pintype "passive"))
      (node (ref "U13") (pin "2") (pinfunction "IO2_2") (pintype "bidirectional"))
    )
    (net (code "33") (name "14P") (class "Default")
      (node (ref "J15") (pin "PWR") (pinfunction "PWR_PWR") (pintype "bidirectional"))
      (node (ref "RA6") (pin "4") (pinfunction "4_4") (pintype "passive"))
      (node (ref "U13") (pin "5") (pinfunction "IO4_5") (pintype "bidirectional"))
    )
    (net (code "34") (name "15N") (class "Default")
      (node (ref "J14") (pin "GND") (pinfunction "GND_GND") (pintype "bidirectional"))
      (node (ref "J14") (pin "GNDBREAK") (pinfunction "GNDBREAK_GNDBREAK") (pintype "bidirectional"))
      (node (ref "RA6") (pin "1") (pinfunction "1_1") (pintype "passive"))
      (node (ref "U12") (pin "4") (pinfunction "IO3_4") (pintype "bidirectional"))
    )
    (net (code "35") (name "15P") (class "Default")
      (node (ref "J14") (pin "PWR") (pinfunction "PWR_PWR") (pintype "bidirectional"))
      (node (ref "RA6") (pin "2") (pinfunction "2_2") (pintype "passive"))
      (node (ref "U13") (pin "1") (pinfunction "IO1_1") (pintype "bidirectional"))
    )
    (net (code "36") (name "16N") (class "Default")
      (node (ref "J13") (pin "GND") (pinfunction "GND_GND") (pintype "bidirectional"))
      (node (ref "J13") (pin "GNDBREAK") (pinfunction "GNDBREAK_GNDBREAK") (pintype "bidirectional"))
      (node (ref "RA5") (pin "3") (pinfunction "3_3") (pintype "passive"))
      (node (ref "U12") (pin "2") (pinfunction "IO2_2") (pintype "bidirectional"))
    )
    (net (code "37") (name "16P") (class "Default")
      (node (ref "J13") (pin "PWR") (pinfunction "PWR_PWR") (pintype "bidirectional"))
      (node (ref "RA5") (pin "4") (pinfunction "4_4") (pintype "passive"))
      (node (ref "U12") (pin "5") (pinfunction "IO4_5") (pintype "bidirectional"))
    )
    (net (code "38") (name "AIN1N") (class "Default")
      (node (ref "CA5") (pin "8") (pinfunction "8_8") (pintype "passive"))
      (node (ref "R45") (pin "8") (pinfunction "8_8") (pintype "passive"))
      (node (ref "U1") (pin "15") (pinfunction "IN1N_15") (pintype "input"))
    )
    (net (code "39") (name "AIN1P") (class "Default")
      (node (ref "CA5") (pin "7") (pinfunction "7_7") (pintype "passive"))
      (node (ref "R45") (pin "7") (pinfunction "7_7") (pintype "passive"))
      (node (ref "U1") (pin "16") (pinfunction "IN1P_16") (pintype "input"))
    )
    (net (code "40") (name "AIN2N") (class "Default")
      (node (ref "CA4") (pin "6") (pinfunction "6_6") (pintype "passive"))
      (node (ref "RA4") (pin "6") (pinfunction "6_6") (pintype "passive"))
      (node (ref "U1") (pin "13") (pinfunction "IN2N_13") (pintype "input"))
    )
    (net (code "41") (name "AIN2P") (class "Default")
      (node (ref "CA4") (pin "5") (pinfunction "5_5") (pintype "passive"))
      (node (ref "RA4") (pin "5") (pinfunction "5_5") (pintype "passive"))
      (node (ref "U1") (pin "14") (pinfunction "IN2P_14") (pintype "input"))
    )
    (net (code "42") (name "AIN3N") (class "Default")
      (node (ref "CA4") (pin "8") (pinfunction "8_8") (pintype "passive"))
      (node (ref "RA4") (pin "8") (pinfunction "8_8") (pintype "passive"))
      (node (ref "U1") (pin "11") (pinfunction "IN3N_11") (pintype "input"))
    )
    (net (code "43") (name "AIN3P") (class "Default")
      (node (ref "CA4") (pin "7") (pinfunction "7_7") (pintype "passive"))
      (node (ref "RA4") (pin "7") (pinfunction "7_7") (pintype "passive"))
      (node (ref "U1") (pin "12") (pinfunction "IN3P_12") (pintype "input"))
    )
    (net (code "44") (name "AIN4N") (class "Default")
      (node (ref "CA3") (pin "6") (pinfunction "6_6") (pintype "passive"))
      (node (ref "RA3") (pin "6") (pinfunction "6_6") (pintype "passive"))
      (node (ref "U1") (pin "9") (pinfunction "IN4N_9") (pintype "input"))
    )
    (net (code "45") (name "AIN4P") (class "Default")
      (node (ref "CA3") (pin "5") (pinfunction "5_5") (pintype "passive"))
      (node (ref "RA3") (pin "5") (pinfunction "5_5") (pintype "passive"))
      (node (ref "U1") (pin "10") (pinfunction "IN4P_10") (pintype "input"))
    )
    (net (code "46") (name "AIN5N") (class "Default")
      (node (ref "CA3") (pin "8") (pinfunction "8_8") (pintype "passive"))
      (node (ref "RA3") (pin "8") (pinfunction "8_8") (pintype "passive"))
      (node (ref "U1") (pin "7") (pinfunction "IN5N_7") (pintype "input"))
    )
    (net (code "47") (name "AIN5P") (class "Default")
      (node (ref "CA3") (pin "7") (pinfunction "7_7") (pintype "passive"))
      (node (ref "RA3") (pin "7") (pinfunction "7_7") (pintype "passive"))
      (node (ref "U1") (pin "8") (pinfunction "IN5P_8") (pintype "input"))
    )
    (net (code "48") (name "AIN6N") (class "Default")
      (node (ref "CA2") (pin "6") (pinfunction "6_6") (pintype "passive"))
      (node (ref "RA2") (pin "6") (pinfunction "6_6") (pintype "passive"))
      (node (ref "U1") (pin "5") (pinfunction "IN6N_5") (pintype "input"))
    )
    (net (code "49") (name "AIN6P") (class "Default")
      (node (ref "CA2") (pin "5") (pinfunction "5_5") (pintype "passive"))
      (node (ref "RA2") (pin "5") (pinfunction "5_5") (pintype "passive"))
      (node (ref "U1") (pin "6") (pinfunction "IN6P_6") (pintype "input"))
    )
    (net (code "50") (name "AIN7N") (class "Default")
      (node (ref "CA2") (pin "8") (pinfunction "8_8") (pintype "passive"))
      (node (ref "RA2") (pin "8") (pinfunction "8_8") (pintype "passive"))
      (node (ref "U1") (pin "3") (pinfunction "IN7N_3") (pintype "input"))
    )
    (net (code "51") (name "AIN7P") (class "Default")
      (node (ref "CA2") (pin "7") (pinfunction "7_7") (pintype "passive"))
      (node (ref "RA2") (pin "7") (pinfunction "7_7") (pintype "passive"))
      (node (ref "U1") (pin "4") (pinfunction "IN7P_4") (pintype "input"))
    )
    (net (code "52") (name "AIN8N") (class "Default")
      (node (ref "CA1") (pin "6") (pinfunction "6_6") (pintype "passive"))
      (node (ref "RA1") (pin "6") (pinfunction "6_6") (pintype "passive"))
      (node (ref "U1") (pin "1") (pinfunction "IN8N_1") (pintype "input"))
    )
    (net (code "53") (name "AIN8P") (class "Default")
      (node (ref "CA1") (pin "5") (pinfunction "5_5") (pintype "passive"))
      (node (ref "RA1") (pin "5") (pinfunction "5_5") (pintype "passive"))
      (node (ref "U1") (pin "2") (pinfunction "IN8P_2") (pintype "input"))
    )
    (net (code "54") (name "AIN9N") (class "Default")
      (node (ref "CA10") (pin "8") (pinfunction "8_8") (pintype "passive"))
      (node (ref "R14") (pin "8") (pinfunction "8_8") (pintype "passive"))
      (node (ref "U2") (pin "15") (pinfunction "IN1N_15") (pintype "input"))
    )
    (net (code "55") (name "AIN9P") (class "Default")
      (node (ref "CA10") (pin "7") (pinfunction "7_7") (pintype "passive"))
      (node (ref "R14") (pin "7") (pinfunction "7_7") (pintype "passive"))
      (node (ref "U2") (pin "16") (pinfunction "IN1P_16") (pintype "input"))
    )
    (net (code "56") (name "AIN10N") (class "Default")
      (node (ref "CA9") (pin "6") (pinfunction "6_6") (pintype "passive"))
      (node (ref "RA8") (pin "6") (pinfunction "6_6") (pintype "passive"))
      (node (ref "U2") (pin "13") (pinfunction "IN2N_13") (pintype "input"))
    )
    (net (code "57") (name "AIN10P") (class "Default")
      (node (ref "CA9") (pin "5") (pinfunction "5_5") (pintype "passive"))
      (node (ref "RA8") (pin "5") (pinfunction "5_5") (pintype "passive"))
      (node (ref "U2") (pin "14") (pinfunction "IN2P_14") (pintype "input"))
    )
    (net (code "58") (name "AIN11N") (class "Default")
      (node (ref "CA9") (pin "8") (pinfunction "8_8") (pintype "passive"))
      (node (ref "RA8") (pin "8") (pinfunction "8_8") (pintype "passive"))
      (node (ref "U2") (pin "11") (pinfunction "IN3N_11") (pintype "input"))
    )
    (net (code "59") (name "AIN11P") (class "Default")
      (node (ref "CA9") (pin "7") (pinfunction "7_7") (pintype "passive"))
      (node (ref "RA8") (pin "7") (pinfunction "7_7") (pintype "passive"))
      (node (ref "U2") (pin "12") (pinfunction "IN3P_12") (pintype "input"))
    )
    (net (code "60") (name "AIN12N") (class "Default")
      (node (ref "CA8") (pin "6") (pinfunction "6_6") (pintype "passive"))
      (node (ref "RA7") (pin "6") (pinfunction "6_6") (pintype "passive"))
      (node (ref "U2") (pin "9") (pinfunction "IN4N_9") (pintype "input"))
    )
    (net (code "61") (name "AIN12P") (class "Default")
      (node (ref "CA8") (pin "5") (pinfunction "5_5") (pintype "passive"))
      (node (ref "RA7") (pin "5") (pinfunction "5_5") (pintype "passive"))
      (node (ref "U2") (pin "10") (pinfunction "IN4P_10") (pintype "input"))
    )
    (net (code "62") (name "AIN13N") (class "Default")
      (node (ref "CA8") (pin "8") (pinfunction "8_8") (pintype "passive"))
      (node (ref "RA7") (pin "8") (pinfunction "8_8") (pintype "passive"))
      (node (ref "U2") (pin "7") (pinfunction "IN5N_7") (pintype "input"))
    )
    (net (code "63") (name "AIN13P") (class "Default")
      (node (ref "CA8") (pin "7") (pinfunction "7_7") (pintype "passive"))
      (node (ref "RA7") (pin "7") (pinfunction "7_7") (pintype "passive"))
      (node (ref "U2") (pin "8") (pinfunction "IN5P_8") (pintype "input"))
    )
    (net (code "64") (name "AIN14N") (class "Default")
      (node (ref "CA7") (pin "6") (pinfunction "6_6") (pintype "passive"))
      (node (ref "RA6") (pin "6") (pinfunction "6_6") (pintype "passive"))
      (node (ref "U2") (pin "5") (pinfunction "IN6N_5") (pintype "input"))
    )
    (net (code "65") (name "AIN14P") (class "Default")
      (node (ref "CA7") (pin "5") (pinfunction "5_5") (pintype "passive"))
      (node (ref "RA6") (pin "5") (pinfunction "5_5") (pintype "passive"))
      (node (ref "U2") (pin "6") (pinfunction "IN6P_6") (pintype "input"))
    )
    (net (code "66") (name "AIN15N") (class "Default")
      (node (ref "CA7") (pin "8") (pinfunction "8_8") (pintype "passive"))
      (node (ref "RA6") (pin "8") (pinfunction "8_8") (pintype "passive"))
      (node (ref "U2") (pin "3") (pinfunction "IN7N_3") (pintype "input"))
    )
    (net (code "67") (name "AIN15P") (class "Default")
      (node (ref "CA7") (pin "7") (pinfunction "7_7") (pintype "passive"))
      (node (ref "RA6") (pin "7") (pinfunction "7_7") (pintype "passive"))
      (node (ref "U2") (pin "4") (pinfunction "IN7P_4") (pintype "input"))
    )
    (net (code "68") (name "AIN16N") (class "Default")
      (node (ref "CA6") (pin "6") (pinfunction "6_6") (pintype "passive"))
      (node (ref "RA5") (pin "6") (pinfunction "6_6") (pintype "passive"))
      (node (ref "U2") (pin "1") (pinfunction "IN8N_1") (pintype "input"))
    )
    (net (code "69") (name "AIN16P") (class "Default")
      (node (ref "CA6") (pin "5") (pinfunction "5_5") (pintype "passive"))
      (node (ref "RA5") (pin "5") (pinfunction "5_5") (pintype "passive"))
      (node (ref "U2") (pin "2") (pinfunction "IN8P_2") (pintype "input"))
    )
    (net (code "70") (name "B1") (class "Default")
      (node (ref "A1") (pin "VB") (pinfunction "VB_VB") (pintype "passive"))
      (node (ref "JP3") (pin "3") (pinfunction "3_3") (pintype "passive"))
    )
    (net (code "71") (name "B2") (class "Default")
      (node (ref "A1") (pin "NR") (pinfunction "NR_NR") (pintype "passive"))
      (node (ref "JP3") (pin "4") (pinfunction "4_4") (pintype "passive"))
    )
    (net (code "72") (name "B5") (class "Default")
      (node (ref "A1") (pin "P$21") (pinfunction "P21_P$21") (pintype "passive"))
      (node (ref "JP2") (pin "1") (pinfunction "1_1") (pintype "passive"))
    )
    (net (code "73") (name "B6") (class "Default")
      (node (ref "A1") (pin "P$23") (pinfunction "P23_P$23") (pintype "passive"))
      (node (ref "JP2") (pin "3") (pinfunction "3_3") (pintype "passive"))
    )
    (net (code "74") (name "B7") (class "Default")
      (node (ref "A1") (pin "P$24") (pinfunction "P24_P$24") (pintype "passive"))
      (node (ref "JP2") (pin "4") (pinfunction "4_4") (pintype "passive"))
    )
    (net (code "75") (name "B8") (class "Default")
      (node (ref "A1") (pin "P$26") (pinfunction "P26_P$26") (pintype "passive"))
      (node (ref "J1") (pin "12") (pinfunction "12_12") (pintype "passive"))
      (node (ref "JP2") (pin "6") (pinfunction "6_6") (pintype "passive"))
    )
    (net (code "76") (name "B10") (class "Default")
      (node (ref "A1") (pin "D+") (pinfunction "D+_D+") (pintype "passive"))
      (node (ref "JP2") (pin "11") (pinfunction "11_11") (pintype "passive"))
    )
    (net (code "77") (name "B11") (class "Default")
      (node (ref "A1") (pin "D-") (pinfunction "D-_D-") (pintype "passive"))
      (node (ref "JP2") (pin "12") (pinfunction "12_12") (pintype "passive"))
    )
    (net (code "78") (name "B12") (class "Default")
      (node (ref "A1") (pin "TD+") (pinfunction "TD+_TD+") (pintype "passive"))
      (node (ref "JP2") (pin "13") (pinfunction "13_13") (pintype "passive"))
    )
    (net (code "79") (name "B13") (class "Default")
      (node (ref "A1") (pin "TD-") (pinfunction "TD-_TD-") (pintype "passive"))
      (node (ref "JP2") (pin "14") (pinfunction "14_14") (pintype "passive"))
    )
    (net (code "80") (name "B14") (class "Default")
      (node (ref "A1") (pin "RD+") (pinfunction "RD+_RD+") (pintype "passive"))
      (node (ref "JP2") (pin "15") (pinfunction "15_15") (pintype "passive"))
    )
    (net (code "81") (name "B15") (class "Default")
      (node (ref "A1") (pin "RD-") (pinfunction "RD-_RD-") (pintype "passive"))
      (node (ref "JP2") (pin "16") (pinfunction "16_16") (pintype "passive"))
    )
    (net (code "82") (name "B16") (class "Default")
      (node (ref "A1") (pin "IF+") (pinfunction "IF+_IF+") (pintype "passive"))
      (node (ref "JP2") (pin "17") (pinfunction "17_17") (pintype "passive"))
    )
    (net (code "83") (name "B17") (class "Default")
      (node (ref "A1") (pin "IF-") (pinfunction "IF-_IF-") (pintype "passive"))
      (node (ref "JP2") (pin "18") (pinfunction "18_18") (pintype "passive"))
    )
    (net (code "84") (name "B18") (class "Default")
      (node (ref "A1") (pin "VU") (pinfunction "VU_VU") (pintype "passive"))
      (node (ref "JP2") (pin "19") (pinfunction "19_19") (pintype "passive"))
    )
    (net (code "85") (name "BATT_SWITCH") (class "Default")
      (node (ref "SW1") (pin "1") (pinfunction "1_1") (pintype "passive"))
      (node (ref "SW2") (pin "3") (pinfunction "3_3") (pintype "passive"))
    )
    (net (code "86") (name "BIAS") (class "Default")
      (node (ref "J21") (pin "GND") (pinfunction "GND_GND") (pintype "bidirectional"))
      (node (ref "J21") (pin "GNDBREAK") (pinfunction "GNDBREAK_GNDBREAK") (pintype "bidirectional"))
      (node (ref "J21") (pin "PWR") (pinfunction "PWR_PWR") (pintype "bidirectional"))
      (node (ref "RA1") (pin "1") (pinfunction "1_1") (pintype "passive"))
      (node (ref "U11") (pin "4") (pinfunction "IO3_4") (pintype "bidirectional"))
    )
    (net (code "87") (name "BIAS_1") (class "Default")
      (node (ref "J23") (pin "GND") (pinfunction "GND_GND") (pintype "bidirectional"))
      (node (ref "J23") (pin "GNDBREAK") (pinfunction "GNDBREAK_GNDBREAK") (pintype "bidirectional"))
      (node (ref "J23") (pin "PWR") (pinfunction "PWR_PWR") (pintype "bidirectional"))
      (node (ref "RA5") (pin "1") (pinfunction "1_1") (pintype "passive"))
      (node (ref "U17") (pin "4") (pinfunction "IO3_4") (pintype "bidirectional"))
    )
    (net (code "88") (name "BIAS_DRV") (class "Default")
      (node (ref "C25") (pin "1") (pinfunction "1_1") (pintype "passive"))
      (node (ref "CA1") (pin "8") (pinfunction "8_8") (pintype "passive"))
      (node (ref "R12") (pin "1") (pinfunction "1_1") (pintype "passive"))
      (node (ref "RA1") (pin "8") (pinfunction "8_8") (pintype "passive"))
    )
    (net (code "89") (name "BIAS_DRV_1") (class "Default")
      (node (ref "C37") (pin "1") (pinfunction "1_1") (pintype "passive"))
      (node (ref "CA6") (pin "8") (pinfunction "8_8") (pintype "passive"))
      (node (ref "R13") (pin "1") (pinfunction "1_1") (pintype "passive"))
      (node (ref "RA5") (pin "8") (pinfunction "8_8") (pintype "passive"))
    )
    (net (code "90") (name "BIAS_INV") (class "Default")
      (node (ref "JP4") (pin "2") (pinfunction "2_2") (pintype "passive"))
      (node (ref "U1") (pin "61") (pinfunction "BIASINV_61") (pintype "bidirectional"))
    )
    (net (code "91") (name "BIAS_INV_1") (class "Default")
      (node (ref "JP5") (pin "2") (pinfunction "2_2") (pintype "passive"))
      (node (ref "U2") (pin "61") (pinfunction "BIASINV_61") (pintype "bidirectional"))
    )
    (net (code "92") (name "BLE_EN") (class "Default")
      (node (ref "A1") (pin "P$17") (pinfunction "P17_P$17") (pintype "passive"))
      (node (ref "JP3") (pin "17") (pinfunction "17_17") (pintype "passive"))
      (node (ref "JP7") (pin "1") (pinfunction "1_1") (pintype "passive"))
    )
    (net (code "93") (name "BLE_RX") (class "Default")
      (node (ref "A1") (pin "P$9") (pinfunction "P9_P$9") (pintype "passive"))
      (node (ref "JP3") (pin "9") (pinfunction "9_9") (pintype "passive"))
      (node (ref "JP7") (pin "5") (pinfunction "5_5") (pintype "passive"))
    )
    (net (code "94") (name "BLE_STATE") (class "Default")
      (node (ref "A1") (pin "P$18") (pinfunction "P18_P$18") (pintype "passive"))
      (node (ref "JP3") (pin "18") (pinfunction "18_18") (pintype "passive"))
      (node (ref "JP7") (pin "6") (pinfunction "6_6") (pintype "passive"))
    )
    (net (code "95") (name "BLE_TX") (class "Default")
      (node (ref "A1") (pin "P$10") (pinfunction "P10_P$10") (pintype "passive"))
      (node (ref "JP3") (pin "10") (pinfunction "10_10") (pintype "passive"))
      (node (ref "JP7") (pin "4") (pinfunction "4_4") (pintype "passive"))
    )
    (net (code "96") (name "CLK_ADS") (class "Default")
      (node (ref "R18") (pin "2") (pinfunction "2_2") (pintype "passive"))
      (node (ref "R19") (pin "2") (pinfunction "2_2") (pintype "passive"))
      (node (ref "U1") (pin "37") (pinfunction "CLK_37") (pintype "input"))
    )
    (net (code "97") (name "DEBUG_1") (class "Default")
      (node (ref "A1") (pin "P$29") (pinfunction "P29_P$29") (pintype "passive"))
      (node (ref "JP2") (pin "9") (pinfunction "9_9") (pintype "passive"))
      (node (ref "R15") (pin "1") (pinfunction "1_1") (pintype "passive"))
    )
    (net (code "98") (name "DEBUG_2") (class "Default")
      (node (ref "A1") (pin "P$25") (pinfunction "P25_P$25") (pintype "passive"))
      (node (ref "JP2") (pin "5") (pinfunction "5_5") (pintype "passive"))
      (node (ref "R16") (pin "1") (pinfunction "1_1") (pintype "passive"))
    )
    (net (code "99") (name "DEBUG_3") (class "Default")
      (node (ref "A1") (pin "P$22") (pinfunction "P22_P$22") (pintype "passive"))
      (node (ref "JP2") (pin "2") (pinfunction "2_2") (pintype "passive"))
      (node (ref "R17") (pin "1") (pinfunction "1_1") (pintype "passive"))
    )
    (net (code "100") (name "GND") (class "Default")
      (node (ref "A1") (pin "GND") (pinfunction "GND_GND") (pintype "passive"))
      (node (ref "C1") (pin "2") (pinfunction "2_2") (pintype "passive"))
      (node (ref "C11") (pin "2") (pinfunction "2_2") (pintype "passive"))
      (node (ref "C12") (pin "2") (pinfunction "2_2") (pintype "passive"))
      (node (ref "C13") (pin "2") (pinfunction "2_2") (pintype "passive"))
      (node (ref "C14") (pin "2") (pinfunction "2_2") (pintype "passive"))
      (node (ref "C15") (pin "2") (pinfunction "2_2") (pintype "passive"))
      (node (ref "C16") (pin "2") (pinfunction "2_2") (pintype "passive"))
      (node (ref "C17") (pin "2") (pinfunction "2_2") (pintype "passive"))
      (node (ref "C18") (pin "2") (pinfunction "2_2") (pintype "passive"))
      (node (ref "C19") (pin "2") (pinfunction "2_2") (pintype "passive"))
      (node (ref "C2") (pin "2") (pinfunction "2_2") (pintype "passive"))
      (node (ref "C20") (pin "2") (pinfunction "2_2") (pintype "passive"))
      (node (ref "C21") (pin "2") (pinfunction "2_2") (pintype "passive"))
      (node (ref "C22") (pin "2") (pinfunction "2_2") (pintype "passive"))
      (node (ref "C23") (pin "2") (pinfunction "2_2") (pintype "passive"))
      (node (ref "C24") (pin "2") (pinfunction "2_2") (pintype "passive"))
      (node (ref "C26") (pin "2") (pinfunction "2_2") (pintype "passive"))
      (node (ref "C27") (pin "2") (pinfunction "2_2") (pintype "passive"))
      (node (ref "C28") (pin "2") (pinfunction "2_2") (pintype "passive"))
      (node (ref "C29") (pin "2") (pinfunction "2_2") (pintype "passive"))
      (node (ref "C3") (pin "2") (pinfunction "2_2") (pintype "passive"))
      (node (ref "C30") (pin "2") (pinfunction "2_2") (pintype "passive"))
      (node (ref "C31") (pin "2") (pinfunction "2_2") (pintype "passive"))
      (node (ref "C32") (pin "2") (pinfunction "2_2") (pintype "passive"))
      (node (ref "C33") (pin "2") (pinfunction "2_2") (pintype "passive"))
      (node (ref "C34") (pin "2") (pinfunction "2_2") (pintype "passive"))
      (node (ref "C35") (pin "2") (pinfunction "2_2") (pintype "passive"))
      (node (ref "C36") (pin "2") (pinfunction "2_2") (pintype "passive"))
      (node (ref "C4") (pin "2") (pinfunction "2_2") (pintype "passive"))
      (node (ref "C5") (pin "2") (pinfunction "2_2") (pintype "passive"))
      (node (ref "C6") (pin "2") (pinfunction "2_2") (pintype "passive"))
      (node (ref "C7") (pin "2") (pinfunction "2_2") (pintype "passive"))
      (node (ref "C9") (pin "2") (pinfunction "2_2") (pintype "passive"))
      (node (ref "CA1") (pin "1") (pinfunction "1_1") (pintype "passive"))
      (node (ref "CA1") (pin "2") (pinfunction "2_2") (pintype "passive"))
      (node (ref "CA1") (pin "3") (pinfunction "3_3") (pintype "passive"))
      (node (ref "CA1") (pin "4") (pinfunction "4_4") (pintype "passive"))
      (node (ref "CA1") (pin "7") (pinfunction "7_7") (pintype "passive"))
      (node (ref "CA10") (pin "1") (pinfunction "1_1") (pintype "passive"))
      (node (ref "CA10") (pin "2") (pinfunction "2_2") (pintype "passive"))
      (node (ref "CA10") (pin "3") (pinfunction "3_3") (pintype "passive"))
      (node (ref "CA10") (pin "4") (pinfunction "4_4") (pintype "passive"))
      (node (ref "CA2") (pin "1") (pinfunction "1_1") (pintype "passive"))
      (node (ref "CA2") (pin "2") (pinfunction "2_2") (pintype "passive"))
      (node (ref "CA2") (pin "3") (pinfunction "3_3") (pintype "passive"))
      (node (ref "CA2") (pin "4") (pinfunction "4_4") (pintype "passive"))
      (node (ref "CA3") (pin "1") (pinfunction "1_1") (pintype "passive"))
      (node (ref "CA3") (pin "2") (pinfunction "2_2") (pintype "passive"))
      (node (ref "CA3") (pin "3") (pinfunction "3_3") (pintype "passive"))
      (node (ref "CA3") (pin "4") (pinfunction "4_4") (pintype "passive"))
      (node (ref "CA4") (pin "1") (pinfunction "1_1") (pintype "passive"))
      (node (ref "CA4") (pin "2") (pinfunction "2_2") (pintype "passive"))
      (node (ref "CA4") (pin "3") (pinfunction "3_3") (pintype "passive"))
      (node (ref "CA4") (pin "4") (pinfunction "4_4") (pintype "passive"))
      (node (ref "CA5") (pin "1") (pinfunction "1_1") (pintype "passive"))
      (node (ref "CA5") (pin "2") (pinfunction "2_2") (pintype "passive"))
      (node (ref "CA5") (pin "3") (pinfunction "3_3") (pintype "passive"))
      (node (ref "CA5") (pin "4") (pinfunction "4_4") (pintype "passive"))
      (node (ref "CA6") (pin "1") (pinfunction "1_1") (pintype "passive"))
      (node (ref "CA6") (pin "2") (pinfunction "2_2") (pintype "passive"))
      (node (ref "CA6") (pin "3") (pinfunction "3_3") (pintype "passive"))
      (node (ref "CA6") (pin "4") (pinfunction "4_4") (pintype "passive"))
      (node (ref "CA6") (pin "7") (pinfunction "7_7") (pintype "passive"))
      (node (ref "CA7") (pin "1") (pinfunction "1_1") (pintype "passive"))
      (node (ref "CA7") (pin "2") (pinfunction "2_2") (pintype "passive"))
      (node (ref "CA7") (pin "3") (pinfunction "3_3") (pintype "passive"))
      (node (ref "CA7") (pin "4") (pinfunction "4_4") (pintype "passive"))
      (node (ref "CA8") (pin "1") (pinfunction "1_1") (pintype "passive"))
      (node (ref "CA8") (pin "2") (pinfunction "2_2") (pintype "passive"))
      (node (ref "CA8") (pin "3") (pinfunction "3_3") (pintype "passive"))
      (node (ref "CA8") (pin "4") (pinfunction "4_4") (pintype "passive"))
      (node (ref "CA9") (pin "1") (pinfunction "1_1") (pintype "passive"))
      (node (ref "CA9") (pin "2") (pinfunction "2_2") (pintype "passive"))
      (node (ref "CA9") (pin "3") (pinfunction "3_3") (pintype "passive"))
      (node (ref "CA9") (pin "4") (pinfunction "4_4") (pintype "passive"))
      (node (ref "D1") (pin "C") (pinfunction "C_C") (pintype "passive"))
      (node (ref "D2") (pin "C") (pinfunction "C_C") (pintype "passive"))
      (node (ref "D3") (pin "C") (pinfunction "C_C") (pintype "passive"))
      (node (ref "D4") (pin "C") (pinfunction "C_C") (pintype "passive"))
      (node (ref "D5") (pin "C") (pinfunction "C_C") (pintype "passive"))
      (node (ref "D6") (pin "C") (pinfunction "C_C") (pintype "passive"))
      (node (ref "D7") (pin "C") (pinfunction "C_C") (pintype "passive"))
      (node (ref "J1") (pin "10") (pinfunction "10_10") (pintype "passive"))
      (node (ref "J1") (pin "6") (pinfunction "6_6") (pintype "passive"))
      (node (ref "J1") (pin "9") (pinfunction "9_9") (pintype "passive"))
      (node (ref "J3") (pin "P$1") (pinfunction "1_P$1") (pintype "passive"))
      (node (ref "J4") (pin "GND") (pinfunction "GND_GND") (pintype "bidirectional"))
      (node (ref "J4") (pin "GNDBREAK") (pinfunction "GNDBREAK_GNDBREAK") (pintype "bidirectional"))
      (node (ref "JP1") (pin "1") (pinfunction "1_1") (pintype "passive"))
      (node (ref "JP3") (pin "1") (pinfunction "1_1") (pintype "passive"))
      (node (ref "JP4") (pin "1") (pinfunction "1_1") (pintype "passive"))
      (node (ref "JP5") (pin "1") (pinfunction "1_1") (pintype "passive"))
      (node (ref "JP7") (pin "3") (pinfunction "3_3") (pintype "passive"))
      (node (ref "R20") (pin "2") (pinfunction "2_2") (pintype "passive"))
      (node (ref "R21") (pin "1") (pinfunction "1_1") (pintype "passive"))
      (node (ref "R24") (pin "2") (pinfunction "2_2") (pintype "passive"))
      (node (ref "R25") (pin "2") (pinfunction "2_2") (pintype "passive"))
      (node (ref "R26") (pin "2") (pinfunction "2_2") (pintype "passive"))
      (node (ref "R27") (pin "1") (pinfunction "1_1") (pintype "passive"))
      (node (ref "R28") (pin "2") (pinfunction "2_2") (pintype "passive"))
      (node (ref "R29") (pin "2") (pinfunction "2_2") (pintype "passive"))
      (node (ref "R3") (pin "2") (pinfunction "2_2") (pintype "passive"))
      (node (ref "R6") (pin "2") (pinfunction "2_2") (pintype "passive"))
      (node (ref "R7") (pin "2") (pinfunction "2_2") (pintype "passive"))
      (node (ref "RA1") (pin "2") (pinfunction "2_2") (pintype "passive"))
      (node (ref "RA1") (pin "7") (pinfunction "7_7") (pintype "passive"))
      (node (ref "RA5") (pin "2") (pinfunction "2_2") (pintype "passive"))
      (node (ref "RA5") (pin "7") (pinfunction "7_7") (pintype "passive"))
      (node (ref "U1") (pin "20") (pinfunction "AVSS_2_20") (pintype "power_in"))
      (node (ref "U1") (pin "23") (pinfunction "AVSS_3_23") (pintype "power_in"))
      (node (ref "U1") (pin "25") (pinfunction "VREFN_25") (pintype "input"))
      (node (ref "U1") (pin "31") (pinfunction "RESV1_31") (pintype "input"))
      (node (ref "U1") (pin "32") (pinfunction "AVSS_4_32") (pintype "power_in"))
      (node (ref "U1") (pin "33") (pinfunction "DGND_2_33") (pintype "power_in"))
      (node (ref "U1") (pin "41") (pinfunction "DAISY_IN_41") (pintype "input"))
      (node (ref "U1") (pin "49") (pinfunction "DGND_3_49") (pintype "power_in"))
      (node (ref "U1") (pin "51") (pinfunction "DGND_51") (pintype "power_in"))
      (node (ref "U1") (pin "53") (pinfunction "AVSS1_53") (pintype "power_in"))
      (node (ref "U1") (pin "57") (pinfunction "AVSS_5_57") (pintype "power_in"))
      (node (ref "U1") (pin "58") (pinfunction "AVSS_58") (pintype "power_in"))
      (node (ref "U1") (pin "64") (pinfunction "RESERVED_64") (pintype "output"))
      (node (ref "U10") (pin "3") (pinfunction "GND_3") (pintype "power_in"))
      (node (ref "U11") (pin "1") (pinfunction "IO1_1") (pintype "bidirectional"))
      (node (ref "U11") (pin "3") (pinfunction "GND_3") (pintype "power_in"))
      (node (ref "U12") (pin "3") (pinfunction "GND_3") (pintype "power_in"))
      (node (ref "U13") (pin "3") (pinfunction "GND_3") (pintype "power_in"))
      (node (ref "U14") (pin "3") (pinfunction "GND_3") (pintype "power_in"))
      (node (ref "U15") (pin "3") (pinfunction "GND_3") (pintype "power_in"))
      (node (ref "U16") (pin "3") (pinfunction "GND_3") (pintype "power_in"))
      (node (ref "U17") (pin "1") (pinfunction "IO1_1") (pintype "bidirectional"))
      (node (ref "U17") (pin "3") (pinfunction "GND_3") (pintype "power_in"))
      (node (ref "U2") (pin "20") (pinfunction "AVSS_2_20") (pintype "power_in"))
      (node (ref "U2") (pin "23") (pinfunction "AVSS_3_23") (pintype "power_in"))
      (node (ref "U2") (pin "25") (pinfunction "VREFN_25") (pintype "input"))
      (node (ref "U2") (pin "31") (pinfunction "RESV1_31") (pintype "input"))
      (node (ref "U2") (pin "32") (pinfunction "AVSS_4_32") (pintype "power_in"))
      (node (ref "U2") (pin "33") (pinfunction "DGND_2_33") (pintype "power_in"))
      (node (ref "U2") (pin "41") (pinfunction "DAISY_IN_41") (pintype "input"))
      (node (ref "U2") (pin "49") (pinfunction "DGND_3_49") (pintype "power_in"))
      (node (ref "U2") (pin "51") (pinfunction "DGND_51") (pintype "power_in"))
      (node (ref "U2") (pin "53") (pinfunction "AVSS1_53") (pintype "power_in"))
      (node (ref "U2") (pin "57") (pinfunction "AVSS_5_57") (pintype "power_in"))
      (node (ref "U2") (pin "58") (pinfunction "AVSS_58") (pintype "power_in"))
      (node (ref "U2") (pin "64") (pinfunction "RESERVED_64") (pintype "output"))
      (node (ref "U3") (pin "11") (pinfunction "PGND2_11") (pintype "passive"))
      (node (ref "U3") (pin "3") (pinfunction "AGND_3") (pintype "passive"))
      (node (ref "U3") (pin "6") (pinfunction "MODE/SYNC_6") (pintype "passive"))
      (node (ref "U3") (pin "9") (pinfunction "PGND1_9") (pintype "passive"))
      (node (ref "U5") (pin "2") (pinfunction "GND_2") (pintype "passive"))
      (node (ref "U6") (pin "3") (pinfunction "GND_3") (pintype "power_in"))
      (node (ref "U7") (pin "3") (pinfunction "GND_3") (pintype "power_in"))
      (node (ref "U8") (pin "3") (pinfunction "GND_3") (pintype "power_in"))
      (node (ref "U9") (pin "3") (pinfunction "GND_3") (pintype "power_in"))
    )
    (net (code "101") (name "MISO_ADS") (class "Default")
      (node (ref "A1") (pin "P$6") (pinfunction "P6_P$6") (pintype "passive"))
      (node (ref "JP3") (pin "6") (pinfunction "6_6") (pintype "passive"))
      (node (ref "U1") (pin "43") (pinfunction "DOUT_43") (pintype "output"))
      (node (ref "U2") (pin "43") (pinfunction "DOUT_43") (pintype "output"))
    )
    (net (code "102") (name "MISO_SD") (class "Default")
      (node (ref "A1") (pin "P$12") (pinfunction "P12_P$12") (pintype "passive"))
      (node (ref "J1") (pin "7") (pinfunction "7_7") (pintype "passive"))
      (node (ref "JP3") (pin "12") (pinfunction "12_12") (pintype "passive"))
    )
    (net (code "103") (name "MOSI_ADS") (class "Default")
      (node (ref "A1") (pin "P$5") (pinfunction "P5_P$5") (pintype "passive"))
      (node (ref "JP3") (pin "5") (pinfunction "5_5") (pintype "passive"))
      (node (ref "U1") (pin "34") (pinfunction "DIN_34") (pintype "input"))
      (node (ref "U2") (pin "34") (pinfunction "DIN_34") (pintype "input"))
    )
    (net (code "104") (name "MOSI_SD") (class "Default")
      (node (ref "A1") (pin "P$11") (pinfunction "P11_P$11") (pintype "passive"))
      (node (ref "J1") (pin "3") (pinfunction "3_3") (pintype "passive"))
      (node (ref "JP3") (pin "11") (pinfunction "11_11") (pintype "passive"))
    )
    (net (code "105") (name "Net-(C10-Pad1)") (class "Default")
      (node (ref "C10") (pin "1") (pinfunction "1_1") (pintype "passive"))
      (node (ref "R5") (pin "2") (pinfunction "2_2") (pintype "passive"))
    )
    (net (code "106") (name "Net-(D1-PadA)") (class "Default")
      (node (ref "D1") (pin "A") (pinfunction "A_A") (pintype "passive"))
      (node (ref "R8") (pin "2") (pinfunction "2_2") (pintype "passive"))
    )
    (net (code "107") (name "Net-(D2-PadA)") (class "Default")
      (node (ref "D2") (pin "A") (pinfunction "A_A") (pintype "passive"))
      (node (ref "R9") (pin "2") (pinfunction "2_2") (pintype "passive"))
    )
    (net (code "108") (name "Net-(D3-PadA)") (class "Default")
      (node (ref "D3") (pin "A") (pinfunction "A_A") (pintype "passive"))
      (node (ref "R10") (pin "2") (pinfunction "2_2") (pintype "passive"))
    )
    (net (code "109") (name "Net-(D4-PadA)") (class "Default")
      (node (ref "D4") (pin "A") (pinfunction "A_A") (pintype "passive"))
      (node (ref "R11") (pin "2") (pinfunction "2_2") (pintype "passive"))
    )
    (net (code "110") (name "Net-(D5-PadA)") (class "Default")
      (node (ref "D5") (pin "A") (pinfunction "A_A") (pintype "passive"))
      (node (ref "R16") (pin "2") (pinfunction "2_2") (pintype "passive"))
    )
    (net (code "111") (name "Net-(D6-PadA)") (class "Default")
      (node (ref "D6") (pin "A") (pinfunction "A_A") (pintype "passive"))
      (node (ref "R17") (pin "2") (pinfunction "2_2") (pintype "passive"))
    )
    (net (code "112") (name "Net-(D7-PadA)") (class "Default")
      (node (ref "D7") (pin "A") (pinfunction "A_A") (pintype "passive"))
      (node (ref "R15") (pin "2") (pinfunction "2_2") (pintype "passive"))
    )
    (net (code "113") (name "Net-(J2-1)") (class "Default")
      (node (ref "J2") (pin "P$1") (pinfunction "1_P$1") (pintype "passive"))
      (node (ref "SW1") (pin "2") (pinfunction "2_2") (pintype "passive"))
    )
    (net (code "114") (name "Net-(JP6-Pad1)") (class "Default")
      (node (ref "JP6") (pin "1") (pinfunction "1_1") (pintype "passive"))
      (node (ref "R18") (pin "1") (pinfunction "1_1") (pintype "passive"))
    )
    (net (code "115") (name "Net-(U1-BIASIN)") (class "Default")
      (node (ref "C25") (pin "2") (pinfunction "2_2") (pintype "passive"))
      (node (ref "R12") (pin "2") (pinfunction "2_2") (pintype "passive"))
      (node (ref "U1") (pin "62") (pinfunction "BIASIN_62") (pintype "input"))
      (node (ref "U1") (pin "63") (pinfunction "BIASOUT_63") (pintype "output"))
    )
    (net (code "116") (name "Net-(U1-BIASREF)") (class "Default")
      (node (ref "R29") (pin "1") (pinfunction "1_1") (pintype "passive"))
      (node (ref "U1") (pin "60") (pinfunction "BIASREF_60") (pintype "input"))
    )
    (net (code "117") (name "Net-(U1-CLKSEL)") (class "Default")
      (node (ref "R22") (pin "1") (pinfunction "1_1") (pintype "passive"))
      (node (ref "U1") (pin "52") (pinfunction "CLKSEL_52") (pintype "input"))
    )
    (net (code "118") (name "Net-(U1-GPIO1)") (class "Default")
      (node (ref "R21") (pin "2") (pinfunction "2_2") (pintype "passive"))
      (node (ref "U1") (pin "42") (pinfunction "GPIO1_42") (pintype "bidirectional"))
    )
    (net (code "119") (name "Net-(U1-GPIO2)") (class "Default")
      (node (ref "R6") (pin "1") (pinfunction "1_1") (pintype "passive"))
      (node (ref "U1") (pin "44") (pinfunction "GPIO2_44") (pintype "bidirectional"))
    )
    (net (code "120") (name "Net-(U1-GPIO3)") (class "Default")
      (node (ref "R7") (pin "1") (pinfunction "1_1") (pintype "passive"))
      (node (ref "U1") (pin "45") (pinfunction "GPIO3_45") (pintype "bidirectional"))
    )
    (net (code "121") (name "Net-(U1-GPIO4)") (class "Default")
      (node (ref "R20") (pin "1") (pinfunction "1_1") (pintype "passive"))
      (node (ref "U1") (pin "46") (pinfunction "GPIO4_46") (pintype "bidirectional"))
    )
    (net (code "122") (name "Net-(U1-VCAP1)") (class "Default")
      (node (ref "C22") (pin "1") (pinfunction "1_1") (pintype "passive"))
      (node (ref "U1") (pin "28") (pinfunction "VCAP1_28") (pintype "passive"))
    )
    (net (code "123") (name "Net-(U1-VCAP2)") (class "Default")
      (node (ref "C21") (pin "1") (pinfunction "1_1") (pintype "passive"))
      (node (ref "U1") (pin "30") (pinfunction "VCAP2_30") (pintype "passive"))
    )
    (net (code "124") (name "Net-(U1-VCAP3)") (class "Default")
      (node (ref "C18") (pin "1") (pinfunction "1_1") (pintype "passive"))
      (node (ref "C19") (pin "1") (pinfunction "1_1") (pintype "passive"))
      (node (ref "U1") (pin "55") (pinfunction "VCAP3_55") (pintype "passive"))
    )
    (net (code "125") (name "Net-(U1-VCAP4)") (class "Default")
      (node (ref "C20") (pin "1") (pinfunction "1_1") (pintype "passive"))
      (node (ref "U1") (pin "26") (pinfunction "VCAP4_26") (pintype "output"))
    )
    (net (code "126") (name "Net-(U2-BIASIN)") (class "Default")
      (node (ref "C37") (pin "2") (pinfunction "2_2") (pintype "passive"))
      (node (ref "R13") (pin "2") (pinfunction "2_2") (pintype "passive"))
      (node (ref "U2") (pin "62") (pinfunction "BIASIN_62") (pintype "input"))
      (node (ref "U2") (pin "63") (pinfunction "BIASOUT_63") (pintype "output"))
    )
    (net (code "127") (name "Net-(U2-BIASREF)") (class "Default")
      (node (ref "R28") (pin "1") (pinfunction "1_1") (pintype "passive"))
      (node (ref "U2") (pin "60") (pinfunction "BIASREF_60") (pintype "input"))
    )
    (net (code "128") (name "Net-(U2-CLK)") (class "Default")
      (node (ref "R19") (pin "1") (pinfunction "1_1") (pintype "passive"))
      (node (ref "U2") (pin "37") (pinfunction "CLK_37") (pintype "input"))
    )
    (net (code "129") (name "Net-(U2-CLKSEL)") (class "Default")
      (node (ref "R23") (pin "1") (pinfunction "1_1") (pintype "passive"))
      (node (ref "U2") (pin "52") (pinfunction "CLKSEL_52") (pintype "input"))
    )
    (net (code "130") (name "Net-(U2-GPIO1)") (class "Default")
      (node (ref "R27") (pin "2") (pinfunction "2_2") (pintype "passive"))
      (node (ref "U2") (pin "42") (pinfunction "GPIO1_42") (pintype "bidirectional"))
    )
    (net (code "131") (name "Net-(U2-GPIO2)") (class "Default")
      (node (ref "R25") (pin "1") (pinfunction "1_1") (pintype "passive"))
      (node (ref "U2") (pin "44") (pinfunction "GPIO2_44") (pintype "bidirectional"))
    )
    (net (code "132") (name "Net-(U2-GPIO3)") (class "Default")
      (node (ref "R24") (pin "1") (pinfunction "1_1") (pintype "passive"))
      (node (ref "U2") (pin "45") (pinfunction "GPIO3_45") (pintype "bidirectional"))
    )
    (net (code "133") (name "Net-(U2-GPIO4)") (class "Default")
      (node (ref "R26") (pin "1") (pinfunction "1_1") (pintype "passive"))
      (node (ref "U2") (pin "46") (pinfunction "GPIO4_46") (pintype "bidirectional"))
    )
    (net (code "134") (name "Net-(U2-VCAP1)") (class "Default")
      (node (ref "C34") (pin "1") (pinfunction "1_1") (pintype "passive"))
      (node (ref "U2") (pin "28") (pinfunction "VCAP1_28") (pintype "passive"))
    )
    (net (code "135") (name "Net-(U2-VCAP2)") (class "Default")
      (node (ref "C33") (pin "1") (pinfunction "1_1") (pintype "passive"))
      (node (ref "U2") (pin "30") (pinfunction "VCAP2_30") (pintype "passive"))
    )
    (net (code "136") (name "Net-(U2-VCAP3)") (class "Default")
      (node (ref "C30") (pin "1") (pinfunction "1_1") (pintype "passive"))
      (node (ref "C31") (pin "1") (pinfunction "1_1") (pintype "passive"))
      (node (ref "U2") (pin "55") (pinfunction "VCAP3_55") (pintype "passive"))
    )
    (net (code "137") (name "Net-(U2-VCAP4)") (class "Default")
      (node (ref "C32") (pin "1") (pinfunction "1_1") (pintype "passive"))
      (node (ref "U2") (pin "26") (pinfunction "VCAP4_26") (pintype "output"))
    )
    (net (code "138") (name "Net-(U2-~{DRDY})") (class "Default")
      (node (ref "R33") (pin "1") (pinfunction "1_1") (pintype "passive"))
      (node (ref "U2") (pin "47") (pinfunction "~{DRDY}_47") (pintype "output"))
    )
    (net (code "139") (name "Net-(U2-~{RESET})") (class "Default")
      (node (ref "R34") (pin "1") (pinfunction "1_1") (pintype "passive"))
      (node (ref "U2") (pin "36") (pinfunction "~{RESET}_36") (pintype "input"))
    )
    (net (code "140") (name "Net-(U3-CBOOT)") (class "Default")
      (node (ref "C8") (pin "2") (pinfunction "2_2") (pintype "passive"))
      (node (ref "R2") (pin "1") (pinfunction "1_1") (pintype "passive"))
      (node (ref "U3") (pin "14") (pinfunction "CBOOT_14") (pintype "passive"))
    )
    (net (code "141") (name "Net-(U3-EN)") (class "Default")
      (node (ref "R1") (pin "1") (pinfunction "1_1") (pintype "passive"))
      (node (ref "U3") (pin "7") (pinfunction "EN_7") (pintype "passive"))
    )
    (net (code "142") (name "Net-(U3-FB)") (class "Default")
      (node (ref "C10") (pin "2") (pinfunction "2_2") (pintype "passive"))
      (node (ref "R3") (pin "1") (pinfunction "1_1") (pintype "passive"))
      (node (ref "R4") (pin "2") (pinfunction "2_2") (pintype "passive"))
      (node (ref "U3") (pin "4") (pinfunction "FB_4") (pintype "passive"))
    )
    (net (code "143") (name "Net-(U3-RBOOT)") (class "Default")
      (node (ref "R2") (pin "2") (pinfunction "2_2") (pintype "passive"))
      (node (ref "U3") (pin "13") (pinfunction "RBOOT_13") (pintype "passive"))
    )
    (net (code "144") (name "Net-(U3-SW)") (class "Default")
      (node (ref "C8") (pin "1") (pinfunction "1_1") (pintype "passive"))
      (node (ref "L1") (pin "1") (pinfunction "1_1") (pintype "passive"))
      (node (ref "U3") (pin "10") (pinfunction "SW_10") (pintype "passive"))
    )
    (net (code "145") (name "Net-(U3-VCC)") (class "Default")
      (node (ref "C9") (pin "1") (pinfunction "1_1") (pintype "passive"))
      (node (ref "U3") (pin "2") (pinfunction "VCC_2") (pintype "power_in"))
    )
    (net (code "146") (name "Net-(U5-BYPASS)") (class "Default")
      (node (ref "C12") (pin "1") (pinfunction "1_1") (pintype "passive"))
      (node (ref "U5") (pin "4") (pinfunction "BYPASS_4") (pintype "passive"))
    )
    (net (code "147") (name "SCK_SD") (class "Default")
      (node (ref "A1") (pin "P$13") (pinfunction "P13_P$13") (pintype "passive"))
      (node (ref "J1") (pin "5") (pinfunction "5_5") (pintype "passive"))
      (node (ref "JP3") (pin "13") (pinfunction "13_13") (pintype "passive"))
    )
    (net (code "148") (name "SCLK_ADS") (class "Default")
      (node (ref "A1") (pin "P$7") (pinfunction "P7_P$7") (pintype "passive"))
      (node (ref "JP3") (pin "7") (pinfunction "7_7") (pintype "passive"))
      (node (ref "U1") (pin "40") (pinfunction "SCLK_40") (pintype "input"))
      (node (ref "U2") (pin "40") (pinfunction "SCLK_40") (pintype "input"))
    )
    (net (code "149") (name "SCL_IMU") (class "Default")
      (node (ref "A1") (pin "P$27") (pinfunction "P27_P$27") (pintype "passive"))
      (node (ref "JP1") (pin "4") (pinfunction "4_4") (pintype "passive"))
      (node (ref "JP2") (pin "7") (pinfunction "7_7") (pintype "passive"))
    )
    (net (code "150") (name "SDA_IMU") (class "Default")
      (node (ref "A1") (pin "P$28") (pinfunction "P28_P$28") (pintype "passive"))
      (node (ref "JP1") (pin "3") (pinfunction "3_3") (pintype "passive"))
      (node (ref "JP2") (pin "8") (pinfunction "8_8") (pintype "passive"))
    )
    (net (code "151") (name "SRB1") (class "Default")
      (node (ref "CA5") (pin "5") (pinfunction "5_5") (pintype "passive"))
      (node (ref "R45") (pin "5") (pinfunction "5_5") (pintype "passive"))
      (node (ref "U1") (pin "17") (pinfunction "SRB1_17") (pintype "bidirectional"))
    )
    (net (code "152") (name "SRB1_1") (class "Default")
      (node (ref "CA10") (pin "5") (pinfunction "5_5") (pintype "passive"))
      (node (ref "R14") (pin "5") (pinfunction "5_5") (pintype "passive"))
      (node (ref "U2") (pin "17") (pinfunction "SRB1_17") (pintype "bidirectional"))
    )
    (net (code "153") (name "SRB1_OUT") (class "Default")
      (node (ref "J22") (pin "PWR") (pinfunction "PWR_PWR") (pintype "bidirectional"))
      (node (ref "R45") (pin "4") (pinfunction "4_4") (pintype "passive"))
      (node (ref "U10") (pin "5") (pinfunction "IO4_5") (pintype "bidirectional"))
    )
    (net (code "154") (name "SRB1_OUT_1") (class "Default")
      (node (ref "J24") (pin "PWR") (pinfunction "PWR_PWR") (pintype "bidirectional"))
      (node (ref "R14") (pin "4") (pinfunction "4_4") (pintype "passive"))
      (node (ref "U16") (pin "5") (pinfunction "IO4_5") (pintype "bidirectional"))
    )
    (net (code "155") (name "SRB2") (class "Default")
      (node (ref "CA5") (pin "6") (pinfunction "6_6") (pintype "passive"))
      (node (ref "R45") (pin "6") (pinfunction "6_6") (pintype "passive"))
      (node (ref "U1") (pin "18") (pinfunction "SRB2_18") (pintype "bidirectional"))
    )
    (net (code "156") (name "SRB2_1") (class "Default")
      (node (ref "CA10") (pin "6") (pinfunction "6_6") (pintype "passive"))
      (node (ref "R14") (pin "6") (pinfunction "6_6") (pintype "passive"))
      (node (ref "U2") (pin "18") (pinfunction "SRB2_18") (pintype "bidirectional"))
    )
    (net (code "157") (name "SRB2_OUT") (class "Default")
      (node (ref "J22") (pin "GND") (pinfunction "GND_GND") (pintype "bidirectional"))
      (node (ref "J22") (pin "GNDBREAK") (pinfunction "GNDBREAK_GNDBREAK") (pintype "bidirectional"))
      (node (ref "R45") (pin "3") (pinfunction "3_3") (pintype "passive"))
      (node (ref "U10") (pin "2") (pinfunction "IO2_2") (pintype "bidirectional"))
    )
    (net (code "158") (name "SRB2_OUT_1") (class "Default")
      (node (ref "J24") (pin "GND") (pinfunction "GND_GND") (pintype "bidirectional"))
      (node (ref "J24") (pin "GNDBREAK") (pinfunction "GNDBREAK_GNDBREAK") (pintype "bidirectional"))
      (node (ref "R14") (pin "3") (pinfunction "3_3") (pintype "passive"))
      (node (ref "U16") (pin "2") (pinfunction "IO2_2") (pintype "bidirectional"))
    )
    (net (code "159") (name "START_ADS") (class "Default")
      (node (ref "A1") (pin "P$16") (pinfunction "P16_P$16") (pintype "passive"))
      (node (ref "JP3") (pin "16") (pinfunction "16_16") (pintype "passive"))
      (node (ref "U1") (pin "38") (pinfunction "START_38") (pintype "input"))
      (node (ref "U2") (pin "38") (pinfunction "START_38") (pintype "input"))
    )
    (net (code "160") (name "VREFP") (class "Default")
      (node (ref "C23") (pin "1") (pinfunction "1_1") (pintype "passive"))
      (node (ref "C24") (pin "1") (pinfunction "1_1") (pintype "passive"))
      (node (ref "JP8") (pin "1") (pinfunction "1_1") (pintype "passive"))
      (node (ref "U1") (pin "24") (pinfunction "VREFP_24") (pintype "bidirectional"))
    )
    (net (code "161") (name "VREFP_1") (class "Default")
      (node (ref "C35") (pin "1") (pinfunction "1_1") (pintype "passive"))
      (node (ref "C36") (pin "1") (pinfunction "1_1") (pintype "passive"))
      (node (ref "JP9") (pin "1") (pinfunction "1_1") (pintype "passive"))
      (node (ref "U2") (pin "24") (pinfunction "VREFP_24") (pintype "bidirectional"))
    )
    (net (code "162") (name "unconnected-(J1-Pad1)") (class "Default")
      (node (ref "J1") (pin "1") (pinfunction "1_1") (pintype "no_connect"))
    )
    (net (code "163") (name "unconnected-(J1-Pad8)") (class "Default")
      (node (ref "J1") (pin "8") (pinfunction "8_8") (pintype "no_connect"))
    )
    (net (code "164") (name "unconnected-(J1-Pad11)") (class "Default")
      (node (ref "J1") (pin "11") (pinfunction "11_11") (pintype "no_connect"))
    )
    (net (code "165") (name "unconnected-(SW2-Pad2)") (class "Default")
      (node (ref "SW2") (pin "2") (pinfunction "2_2") (pintype "passive"))
    )
    (net (code "166") (name "unconnected-(U1-NC-Pad29)") (class "Default")
      (node (ref "U1") (pin "29") (pinfunction "NC_29") (pintype "no_connect"))
    )
    (net (code "167") (name "unconnected-(U1-NC_2-Pad27)") (class "Default")
      (node (ref "U1") (pin "27") (pinfunction "NC_2_27") (pintype "no_connect"))
    )
    (net (code "168") (name "unconnected-(U2-NC-Pad29)") (class "Default")
      (node (ref "U2") (pin "29") (pinfunction "NC_29") (pintype "no_connect"))
    )
    (net (code "169") (name "unconnected-(U2-NC_2-Pad27)") (class "Default")
      (node (ref "U2") (pin "27") (pinfunction "NC_2_27") (pintype "no_connect"))
    )
    (net (code "170") (name "unconnected-(U3-PGOOD-Pad5)") (class "Default")
      (node (ref "U3") (pin "5") (pinfunction "PGOOD_5") (pintype "no_connect"))
    )
    (net (code "171") (name "unconnected-(U6-IO1-Pad1)") (class "Default")
      (node (ref "U6") (pin "1") (pinfunction "IO1_1") (pintype "bidirectional"))
    )
    (net (code "172") (name "unconnected-(U6-NC-Pad6)") (class "Default")
      (node (ref "U6") (pin "6") (pinfunction "NC_6") (pintype "no_connect"))
    )
    (net (code "173") (name "unconnected-(U7-NC-Pad6)") (class "Default")
      (node (ref "U7") (pin "6") (pinfunction "NC_6") (pintype "no_connect"))
    )
    (net (code "174") (name "unconnected-(U8-NC-Pad6)") (class "Default")
      (node (ref "U8") (pin "6") (pinfunction "NC_6") (pintype "no_connect"))
    )
    (net (code "175") (name "unconnected-(U9-NC-Pad6)") (class "Default")
      (node (ref "U9") (pin "6") (pinfunction "NC_6") (pintype "no_connect"))
    )
    (net (code "176") (name "unconnected-(U10-IO3-Pad4)") (class "Default")
      (node (ref "U10") (pin "4") (pinfunction "IO3_4") (pintype "bidirectional"))
    )
    (net (code "177") (name "unconnected-(U10-NC-Pad6)") (class "Default")
      (node (ref "U10") (pin "6") (pinfunction "NC_6") (pintype "no_connect"))
    )
    (net (code "178") (name "unconnected-(U11-IO4-Pad5)") (class "Default")
      (node (ref "U11") (pin "5") (pinfunction "IO4_5") (pintype "bidirectional"))
    )
    (net (code "179") (name "unconnected-(U11-NC-Pad6)") (class "Default")
      (node (ref "U11") (pin "6") (pinfunction "NC_6") (pintype "no_connect"))
    )
    (net (code "180") (name "unconnected-(U12-IO1-Pad1)") (class "Default")
      (node (ref "U12") (pin "1") (pinfunction "IO1_1") (pintype "bidirectional"))
    )
    (net (code "181") (name "unconnected-(U12-NC-Pad6)") (class "Default")
      (node (ref "U12") (pin "6") (pinfunction "NC_6") (pintype "no_connect"))
    )
    (net (code "182") (name "unconnected-(U13-NC-Pad6)") (class "Default")
      (node (ref "U13") (pin "6") (pinfunction "NC_6") (pintype "no_connect"))
    )
    (net (code "183") (name "unconnected-(U14-NC-Pad6)") (class "Default")
      (node (ref "U14") (pin "6") (pinfunction "NC_6") (pintype "no_connect"))
    )
    (net (code "184") (name "unconnected-(U15-NC-Pad6)") (class "Default")
      (node (ref "U15") (pin "6") (pinfunction "NC_6") (pintype "no_connect"))
    )
    (net (code "185") (name "unconnected-(U16-IO3-Pad4)") (class "Default")
      (node (ref "U16") (pin "4") (pinfunction "IO3_4") (pintype "bidirectional"))
    )
    (net (code "186") (name "unconnected-(U16-NC-Pad6)") (class "Default")
      (node (ref "U16") (pin "6") (pinfunction "NC_6") (pintype "no_connect"))
    )
    (net (code "187") (name "unconnected-(U17-IO4-Pad5)") (class "Default")
      (node (ref "U17") (pin "5") (pinfunction "IO4_5") (pintype "bidirectional"))
    )
    (net (code "188") (name "unconnected-(U17-NC-Pad6)") (class "Default")
      (node (ref "U17") (pin "6") (pinfunction "NC_6") (pintype "no_connect"))
    )
    (net (code "189") (name "~{CS}_ADS_0") (class "Default")
      (node (ref "A1") (pin "P$15") (pinfunction "P15_P$15") (pintype "passive"))
      (node (ref "JP3") (pin "15") (pinfunction "15_15") (pintype "passive"))
      (node (ref "R31") (pin "1") (pinfunction "1_1") (pintype "passive"))
      (node (ref "U1") (pin "39") (pinfunction "~{CS}_39") (pintype "input"))
    )
    (net (code "190") (name "~{CS}_ADS_1") (class "Default")
      (node (ref "A1") (pin "P$20") (pinfunction "P20_P$20") (pintype "passive"))
      (node (ref "JP3") (pin "20") (pinfunction "20_20") (pintype "passive"))
      (node (ref "R32") (pin "1") (pinfunction "1_1") (pintype "passive"))
      (node (ref "U2") (pin "39") (pinfunction "~{CS}_39") (pintype "input"))
    )
    (net (code "191") (name "~{CS}_SD") (class "Default")
      (node (ref "A1") (pin "P$14") (pinfunction "P14_P$14") (pintype "passive"))
      (node (ref "J1") (pin "2") (pinfunction "2_2") (pintype "passive"))
      (node (ref "JP3") (pin "14") (pinfunction "14_14") (pintype "passive"))
    )
    (net (code "192") (name "~{DRDY}_ADS_0") (class "Default")
      (node (ref "A1") (pin "P$8") (pinfunction "P8_P$8") (pintype "passive"))
      (node (ref "JP3") (pin "8") (pinfunction "8_8") (pintype "passive"))
      (node (ref "U1") (pin "47") (pinfunction "~{DRDY}_47") (pintype "output"))
    )
    (net (code "193") (name "~{DRDY}_ADS_1") (class "Default")
      (node (ref "A1") (pin "P$30") (pinfunction "P30_P$30") (pintype "passive"))
      (node (ref "JP2") (pin "10") (pinfunction "10_10") (pintype "passive"))
      (node (ref "R33") (pin "2") (pinfunction "2_2") (pintype "passive"))
    )
    (net (code "194") (name "~{RESET}_ADS") (class "Default")
      (node (ref "A1") (pin "P$19") (pinfunction "P19_P$19") (pintype "passive"))
      (node (ref "JP3") (pin "19") (pinfunction "19_19") (pintype "passive"))
      (node (ref "R30") (pin "1") (pinfunction "1_1") (pintype "passive"))
      (node (ref "R34") (pin "2") (pinfunction "2_2") (pintype "passive"))
      (node (ref "U1") (pin "36") (pinfunction "~{RESET}_36") (pintype "input"))
    )
  )
)
